# TK90X.net
KiCad netlist of a schematic drawn in EAGLE
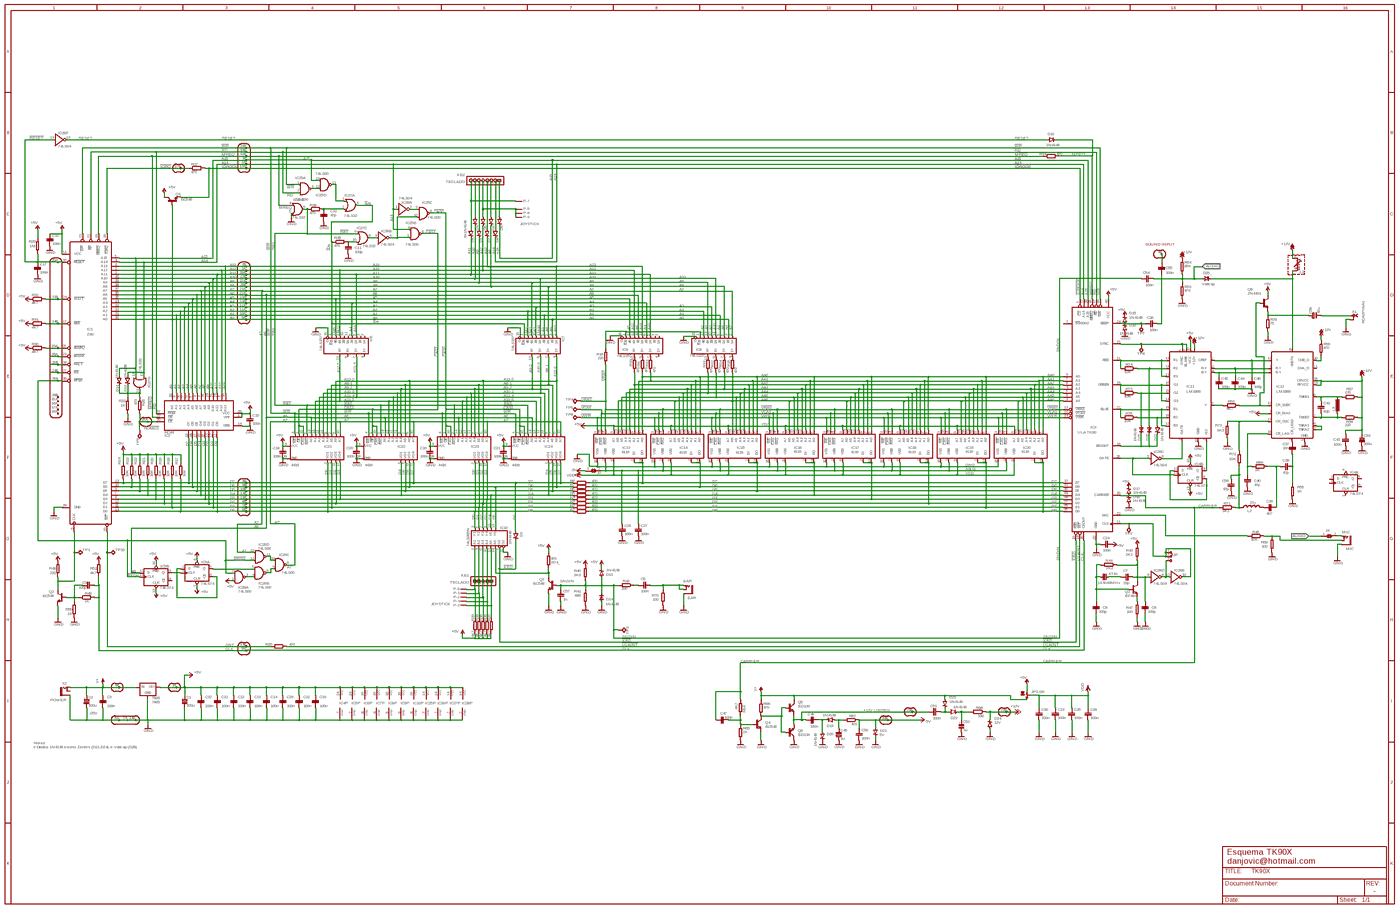
[diagram p0: schematic, sheet 1, overview]
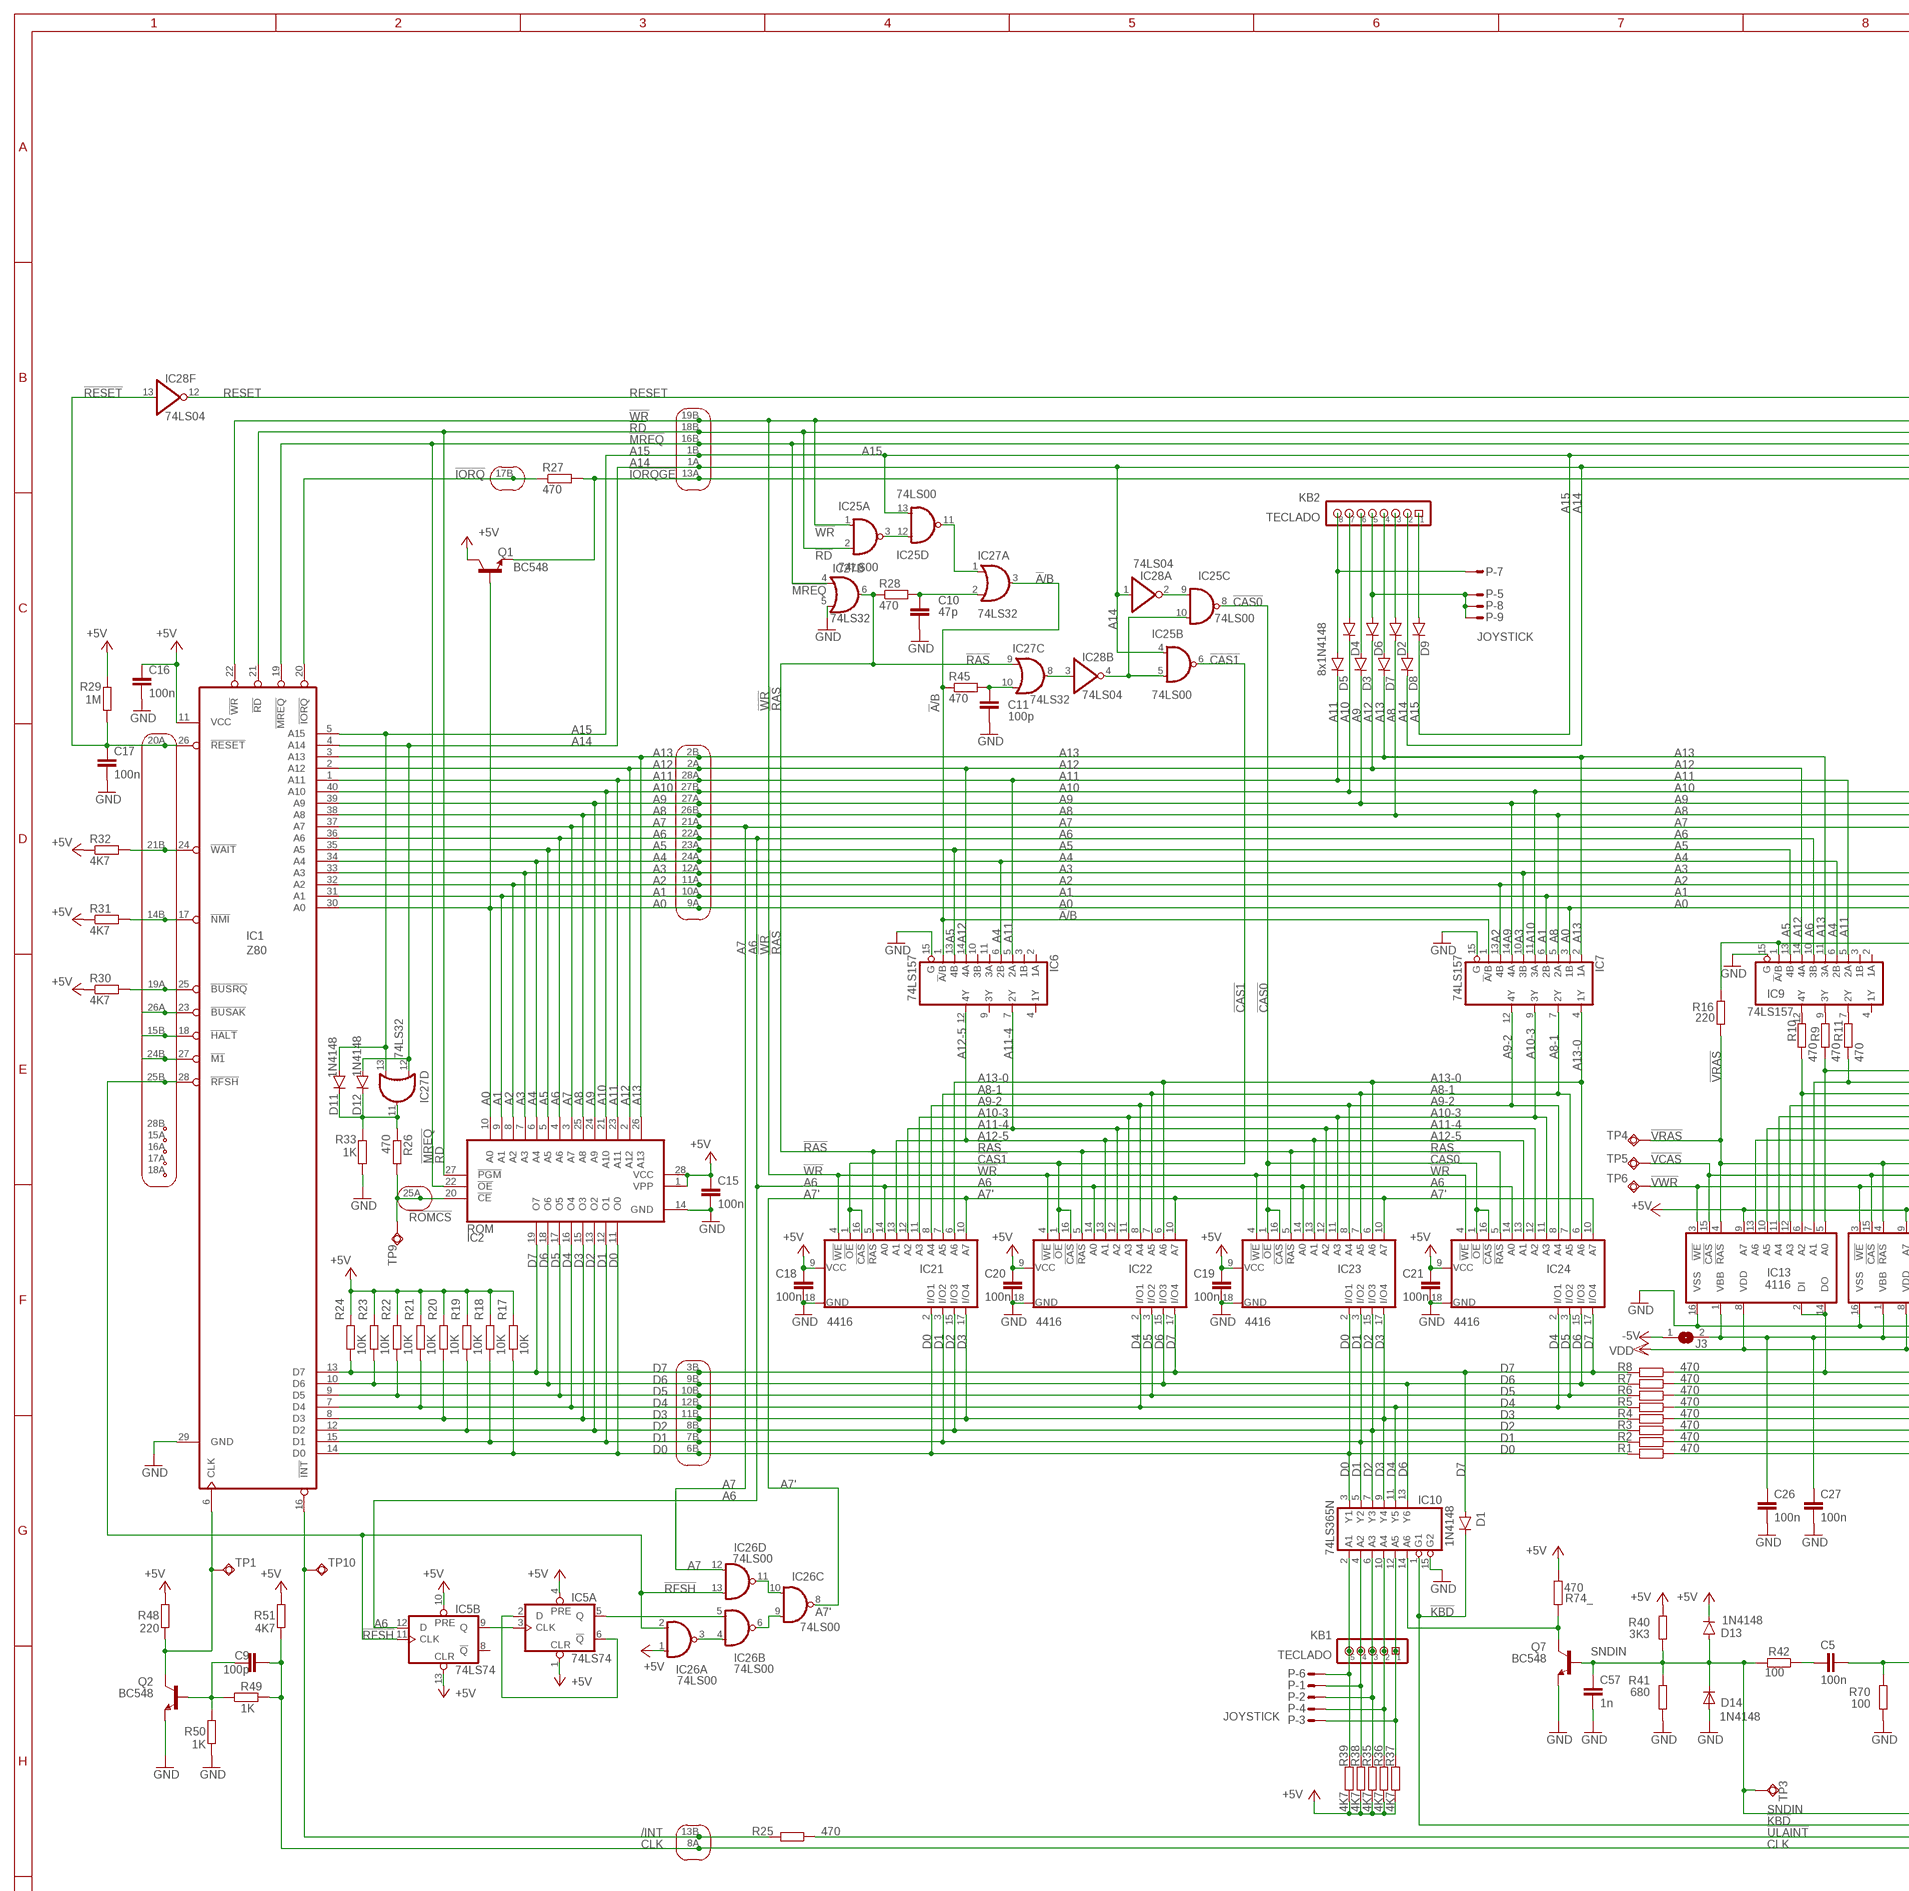
[diagram p1: schematic, sheet 1, part 1 of 4]
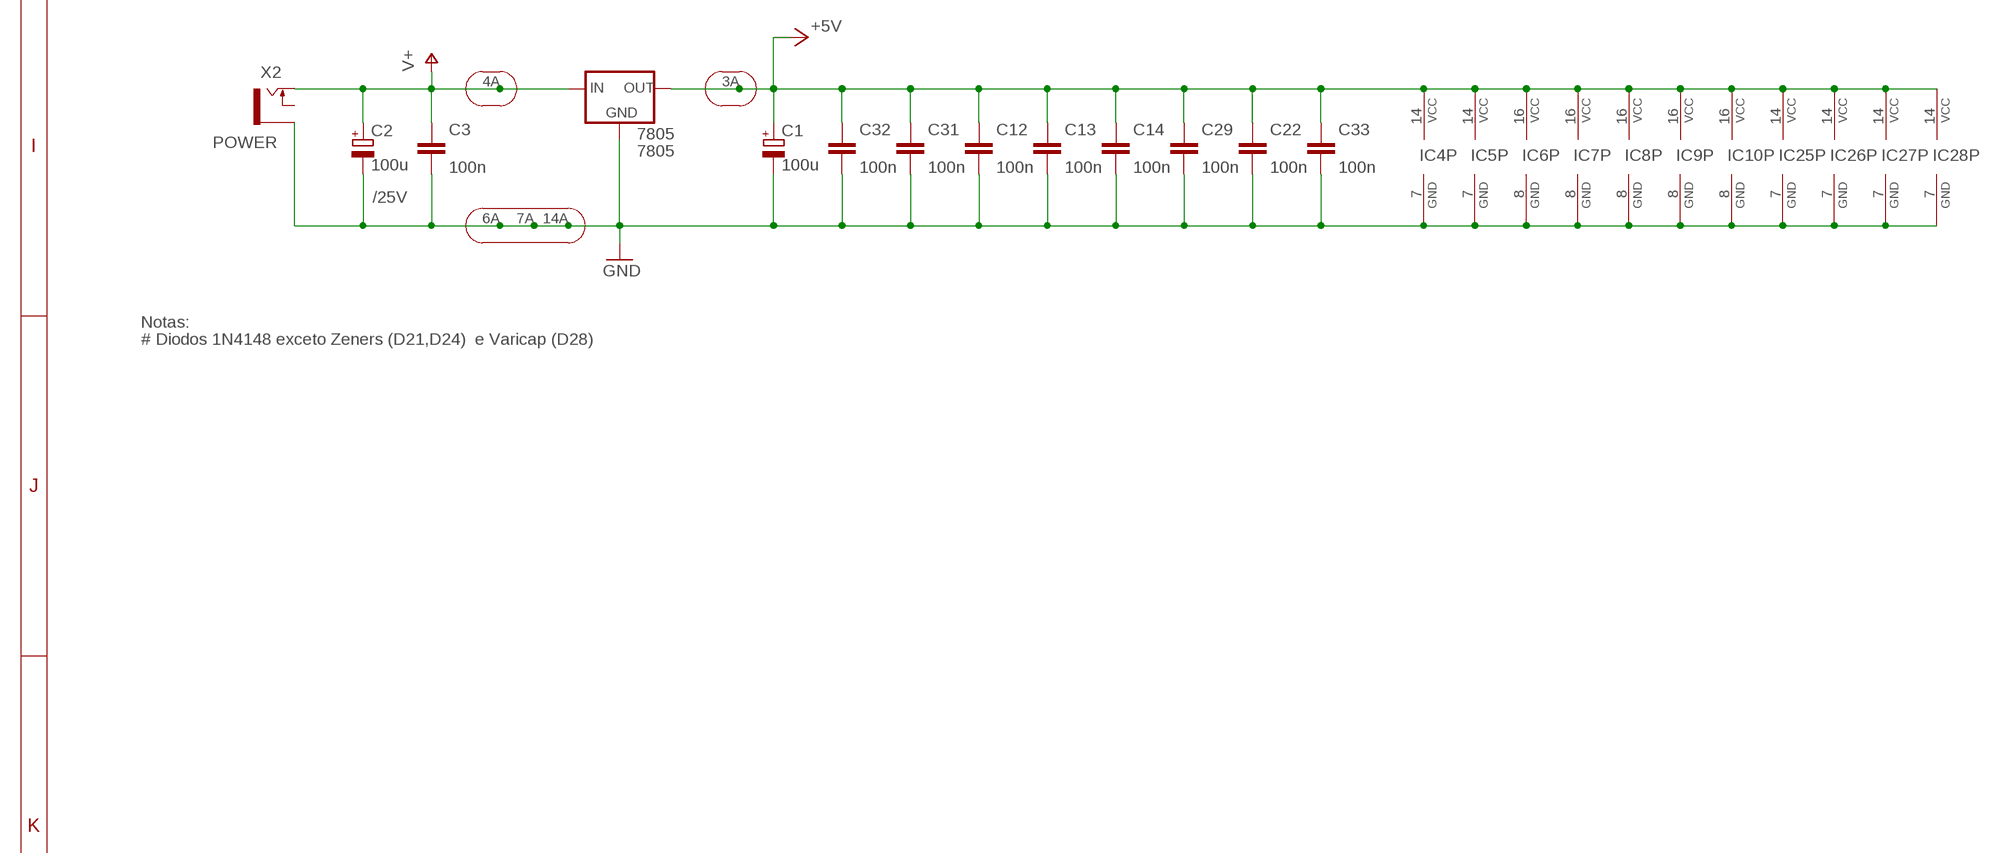
[diagram p2: schematic, sheet 1, part 2 of 4]
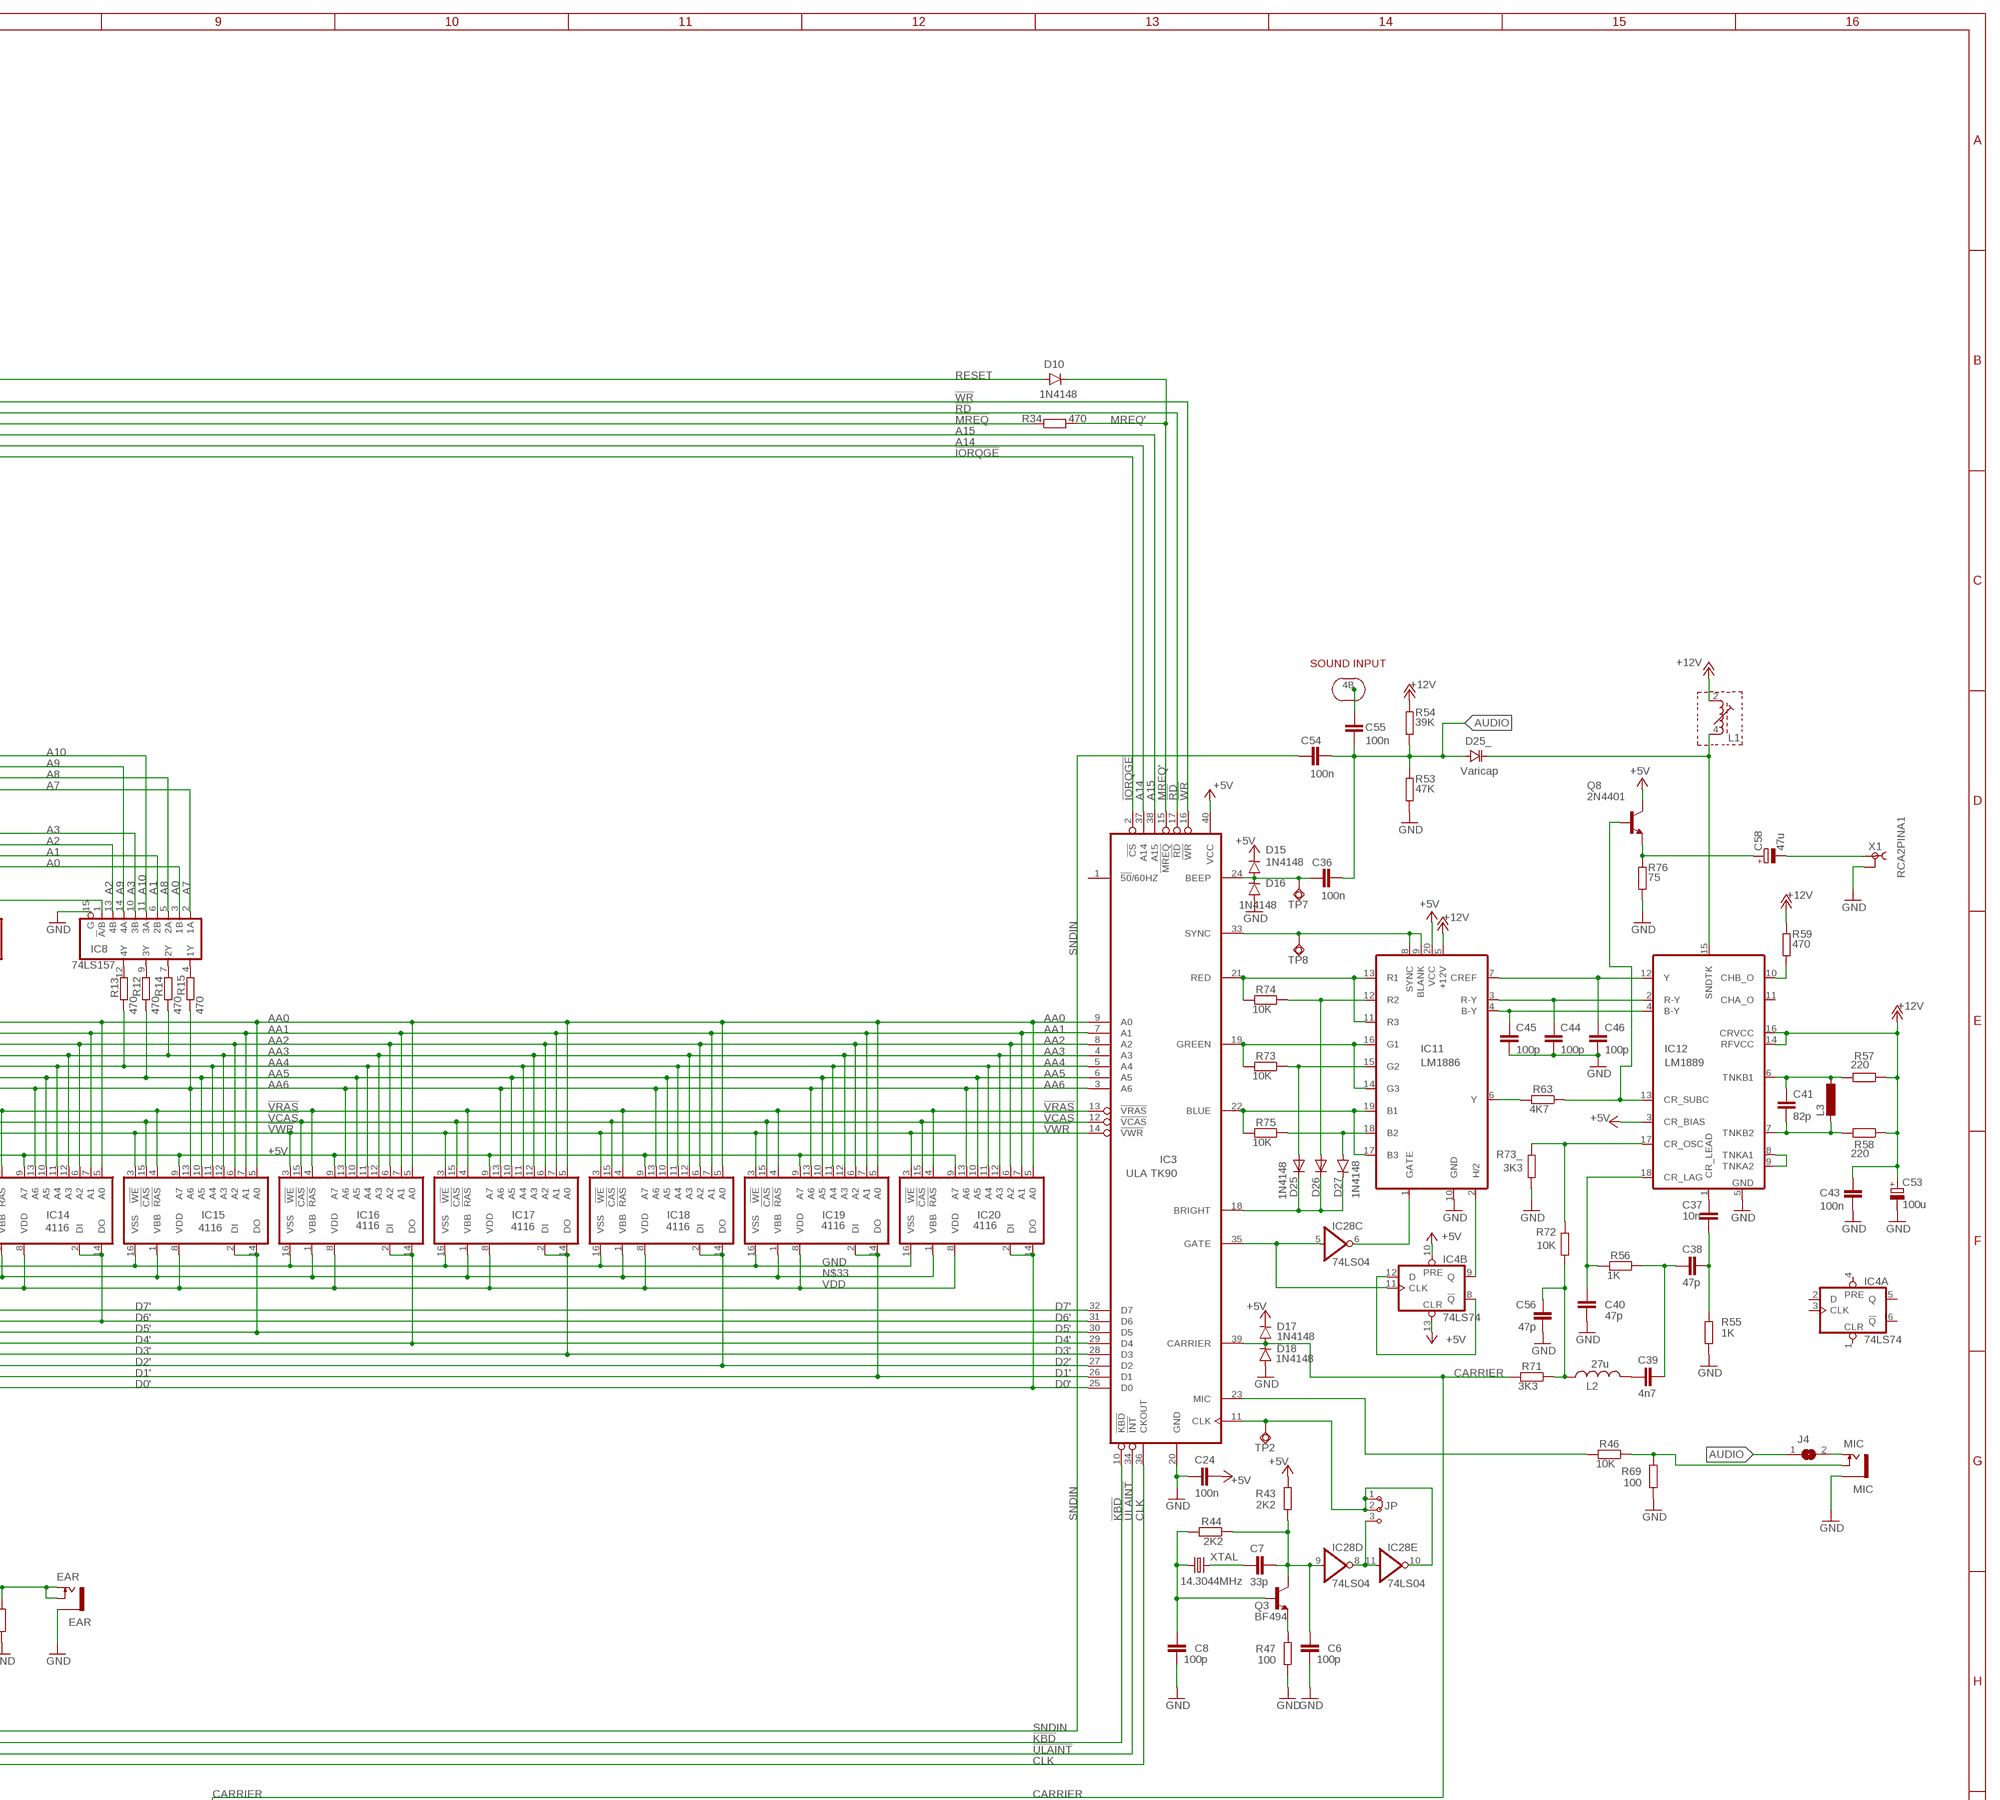
[diagram p3: schematic, sheet 1, part 3 of 4]
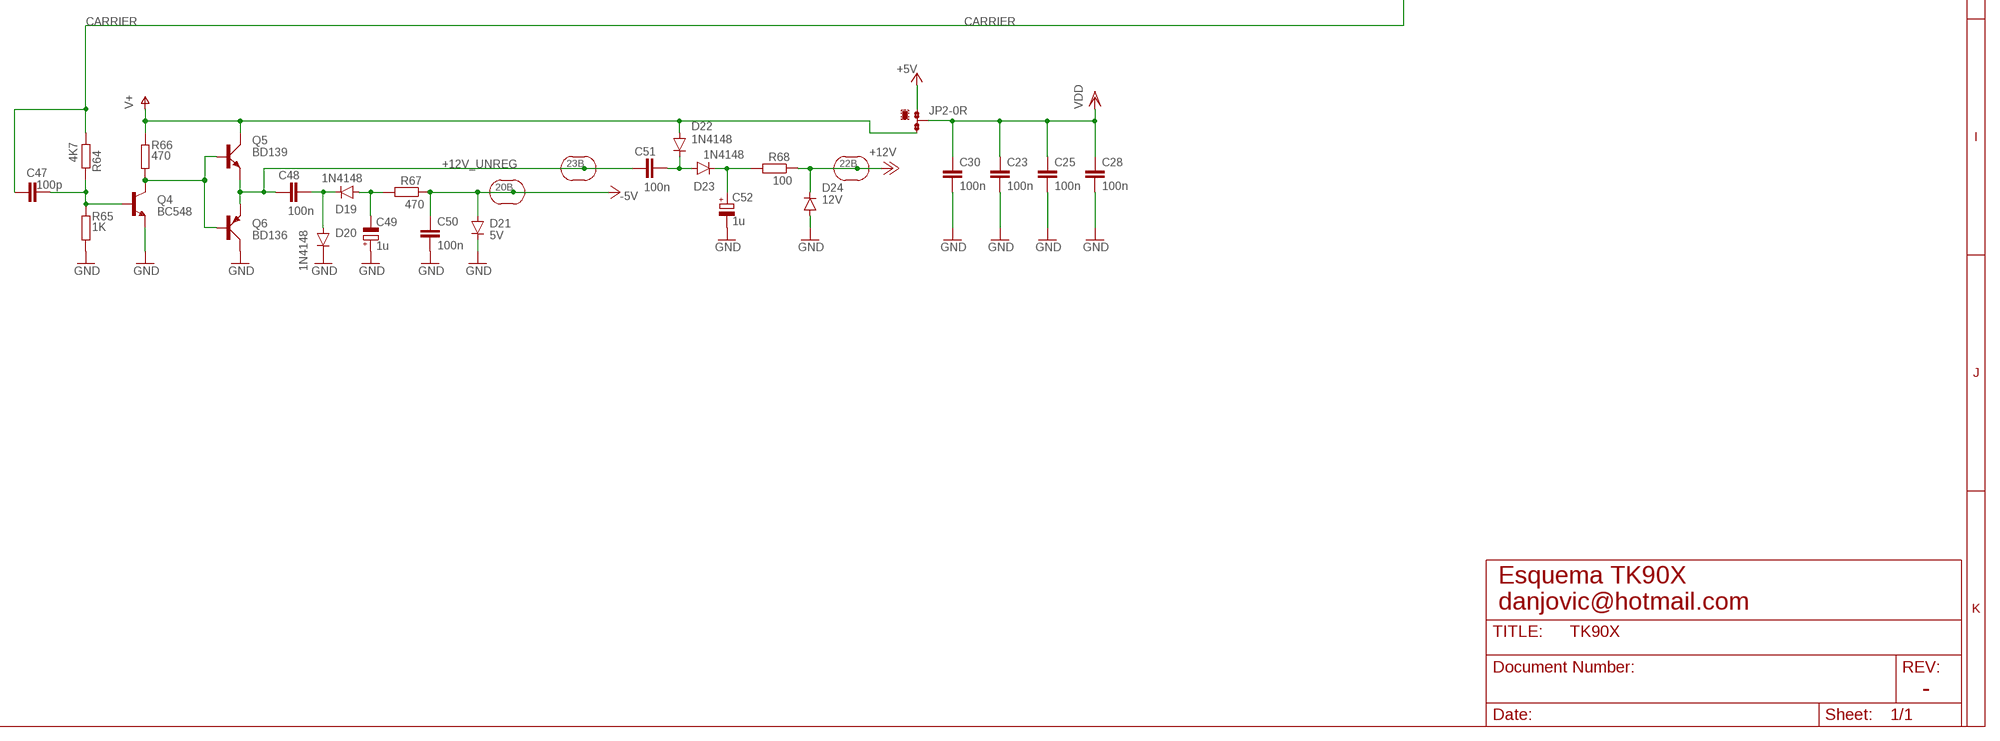
[diagram p4: schematic, sheet 1, part 4 of 4]

(export (version "E")
  (design (tool "Eeschema 10.0.6"))
  (components
    (comp (ref "7805")
      (value "7805")
      (footprint "eagle-import:78XXL")
      (libsource (lib "eagle-import") (part "78XXL"))
    )
    (comp (ref "C1")
      (value "100u")
      (footprint "eagle-import:E5-8,5")
      (libsource (lib "eagle-import") (part "CPOL-EUE5-8.5"))
    )
    (comp (ref "C2")
      (value "100u")
      (footprint "eagle-import:E5-8,5")
      (libsource (lib "eagle-import") (part "CPOL-EUE5-8.5"))
    )
    (comp (ref "C3")
      (value "100n")
      (footprint "eagle-import:C050-024X044")
      (libsource (lib "eagle-import") (part "C-EU050-024X044"))
    )
    (comp (ref "C5")
      (value "100n")
      (footprint "eagle-import:C050-024X044")
      (libsource (lib "eagle-import") (part "C-EU050-024X044"))
    )
    (comp (ref "C6")
      (value "100p")
      (footprint "eagle-import:C050-024X044")
      (libsource (lib "eagle-import") (part "C-EU050-024X044"))
    )
    (comp (ref "C7")
      (value "33p")
      (footprint "eagle-import:C050-024X044")
      (libsource (lib "eagle-import") (part "C-EU050-024X044"))
    )
    (comp (ref "C8")
      (value "100p")
      (footprint "eagle-import:C050-024X044")
      (libsource (lib "eagle-import") (part "C-EU050-024X044"))
    )
    (comp (ref "C9")
      (value "100p")
      (footprint "eagle-import:C050-024X044")
      (libsource (lib "eagle-import") (part "C-EU050-024X044"))
    )
    (comp (ref "C10")
      (value "47p")
      (footprint "eagle-import:C050-024X044")
      (libsource (lib "eagle-import") (part "C-EU050-024X044"))
    )
    (comp (ref "C11")
      (value "100p")
      (footprint "eagle-import:C050-024X044")
      (libsource (lib "eagle-import") (part "C-EU050-024X044"))
    )
    (comp (ref "C12")
      (value "100n")
      (footprint "eagle-import:C050-024X044")
      (libsource (lib "eagle-import") (part "C-EU050-024X044"))
    )
    (comp (ref "C13")
      (value "100n")
      (footprint "eagle-import:C050-024X044")
      (libsource (lib "eagle-import") (part "C-EU050-024X044"))
    )
    (comp (ref "C14")
      (value "100n")
      (footprint "eagle-import:C050-024X044")
      (libsource (lib "eagle-import") (part "C-EU050-024X044"))
    )
    (comp (ref "C15")
      (value "100n")
      (footprint "eagle-import:C050-024X044")
      (libsource (lib "eagle-import") (part "C-EU050-024X044"))
    )
    (comp (ref "C16")
      (value "100n")
      (footprint "eagle-import:C050-024X044")
      (libsource (lib "eagle-import") (part "C-EU050-024X044"))
    )
    (comp (ref "C17")
      (value "100n")
      (footprint "eagle-import:C050-024X044")
      (libsource (lib "eagle-import") (part "C-EU050-024X044"))
    )
    (comp (ref "C18")
      (value "100n")
      (footprint "eagle-import:C050-024X044")
      (libsource (lib "eagle-import") (part "C-EU050-024X044"))
    )
    (comp (ref "C19")
      (value "100n")
      (footprint "eagle-import:C050-024X044")
      (libsource (lib "eagle-import") (part "C-EU050-024X044"))
    )
    (comp (ref "C20")
      (value "100n")
      (footprint "eagle-import:C050-024X044")
      (libsource (lib "eagle-import") (part "C-EU050-024X044"))
    )
    (comp (ref "C21")
      (value "100n")
      (footprint "eagle-import:C050-024X044")
      (libsource (lib "eagle-import") (part "C-EU050-024X044"))
    )
    (comp (ref "C22")
      (value "100n")
      (footprint "eagle-import:C050-024X044")
      (libsource (lib "eagle-import") (part "C-EU050-024X044"))
    )
    (comp (ref "C23")
      (value "100n")
      (footprint "eagle-import:C050-024X044")
      (libsource (lib "eagle-import") (part "C-EU050-024X044"))
    )
    (comp (ref "C24")
      (value "100n")
      (footprint "eagle-import:C050-024X044")
      (libsource (lib "eagle-import") (part "C-EU050-024X044"))
    )
    (comp (ref "C25")
      (value "100n")
      (footprint "eagle-import:C050-024X044")
      (libsource (lib "eagle-import") (part "C-EU050-024X044"))
    )
    (comp (ref "C26")
      (value "100n")
      (footprint "eagle-import:C050-024X044")
      (libsource (lib "eagle-import") (part "C-EU050-024X044"))
    )
    (comp (ref "C27")
      (value "100n")
      (footprint "eagle-import:C050-024X044")
      (libsource (lib "eagle-import") (part "C-EU050-024X044"))
    )
    (comp (ref "C28")
      (value "100n")
      (footprint "eagle-import:C050-024X044")
      (libsource (lib "eagle-import") (part "C-EU050-024X044"))
    )
    (comp (ref "C29")
      (value "100n")
      (footprint "eagle-import:C050-024X044")
      (libsource (lib "eagle-import") (part "C-EU050-024X044"))
    )
    (comp (ref "C30")
      (value "100n")
      (footprint "eagle-import:C050-024X044")
      (libsource (lib "eagle-import") (part "C-EU050-024X044"))
    )
    (comp (ref "C31")
      (value "100n")
      (footprint "eagle-import:C050-024X044")
      (libsource (lib "eagle-import") (part "C-EU050-024X044"))
    )
    (comp (ref "C32")
      (value "100n")
      (footprint "eagle-import:C050-024X044")
      (libsource (lib "eagle-import") (part "C-EU050-024X044"))
    )
    (comp (ref "C33")
      (value "100n")
      (footprint "eagle-import:C050-024X044")
      (libsource (lib "eagle-import") (part "C-EU050-024X044"))
    )
    (comp (ref "C36")
      (value "100n")
      (footprint "eagle-import:C050-024X044")
      (libsource (lib "eagle-import") (part "C-EU050-024X044"))
    )
    (comp (ref "C37")
      (value "10n")
      (footprint "eagle-import:C050-024X044")
      (libsource (lib "eagle-import") (part "C-EU050-024X044"))
    )
    (comp (ref "C38")
      (value "47p")
      (footprint "eagle-import:C050-024X044")
      (libsource (lib "eagle-import") (part "C-EU050-024X044"))
    )
    (comp (ref "C39")
      (value "4n7")
      (footprint "eagle-import:C050-024X044")
      (libsource (lib "eagle-import") (part "C-EU050-024X044"))
    )
    (comp (ref "C40")
      (value "47p")
      (footprint "eagle-import:C050-024X044")
      (libsource (lib "eagle-import") (part "C-EU050-024X044"))
    )
    (comp (ref "C41")
      (value "82p")
      (footprint "eagle-import:C050-024X044")
      (libsource (lib "eagle-import") (part "C-EU050-024X044"))
    )
    (comp (ref "C43")
      (value "100n")
      (footprint "eagle-import:C050-024X044")
      (libsource (lib "eagle-import") (part "C-EU050-024X044"))
    )
    (comp (ref "C44")
      (value "100p")
      (footprint "eagle-import:C050-024X044")
      (libsource (lib "eagle-import") (part "C-EU050-024X044"))
    )
    (comp (ref "C45")
      (value "100p")
      (footprint "eagle-import:C050-024X044")
      (libsource (lib "eagle-import") (part "C-EU050-024X044"))
    )
    (comp (ref "C46")
      (value "100p")
      (footprint "eagle-import:C050-024X044")
      (libsource (lib "eagle-import") (part "C-EU050-024X044"))
    )
    (comp (ref "C47")
      (value "100p")
      (footprint "eagle-import:C050-024X044")
      (libsource (lib "eagle-import") (part "C-EU050-024X044"))
    )
    (comp (ref "C48")
      (value "100n")
      (footprint "eagle-import:C050-024X044")
      (libsource (lib "eagle-import") (part "C-EU050-024X044"))
    )
    (comp (ref "C49")
      (value "1u")
      (footprint "eagle-import:E2-4")
      (libsource (lib "eagle-import") (part "CPOL-EUE2-4"))
    )
    (comp (ref "C50")
      (value "100n")
      (footprint "eagle-import:C050-024X044")
      (libsource (lib "eagle-import") (part "C-EU050-024X044"))
    )
    (comp (ref "C51")
      (value "100n")
      (footprint "eagle-import:C050-024X044")
      (libsource (lib "eagle-import") (part "C-EU050-024X044"))
    )
    (comp (ref "C52")
      (value "1u")
      (footprint "eagle-import:E2-5")
      (libsource (lib "eagle-import") (part "CPOL-EUE2-5"))
    )
    (comp (ref "C53")
      (value "100u")
      (footprint "eagle-import:E5-4")
      (libsource (lib "eagle-import") (part "CPOL-EUE5-4"))
    )
    (comp (ref "C54")
      (value "100n")
      (footprint "eagle-import:C050-024X044")
      (libsource (lib "eagle-import") (part "C-EU050-024X044"))
    )
    (comp (ref "C55")
      (value "100n")
      (footprint "eagle-import:C050-024X044")
      (libsource (lib "eagle-import") (part "C-EU050-024X044"))
    )
    (comp (ref "C56")
      (value "47p")
      (footprint "eagle-import:C050-024X044")
      (libsource (lib "eagle-import") (part "C-EU050-024X044"))
    )
    (comp (ref "C57")
      (value "1n")
      (footprint "eagle-import:C050-024X044")
      (libsource (lib "eagle-import") (part "C-EU050-024X044"))
    )
    (comp (ref "C58")
      (value "47u")
      (footprint "eagle-import:E5-4")
      (libsource (lib "eagle-import") (part "CPOL-EUE5-4"))
    )
    (comp (ref "D1")
      (value "1N4148")
      (footprint "eagle-import:DO35-12")
      (libsource (lib "eagle-import") (part "DDO35-12"))
    )
    (comp (ref "D2")
      (value "1N4148")
      (footprint "eagle-import:DO35-12")
      (libsource (lib "eagle-import") (part "DDO35-12"))
    )
    (comp (ref "D3")
      (value "1N4148")
      (footprint "eagle-import:DO35-12")
      (libsource (lib "eagle-import") (part "DDO35-12"))
    )
    (comp (ref "D4")
      (value "1N4148")
      (footprint "eagle-import:DO35-12")
      (libsource (lib "eagle-import") (part "DDO35-12"))
    )
    (comp (ref "D5")
      (value "1N4148")
      (footprint "eagle-import:DO35-12")
      (libsource (lib "eagle-import") (part "DDO35-12"))
    )
    (comp (ref "D6")
      (value "1N4148")
      (footprint "eagle-import:DO35-12")
      (libsource (lib "eagle-import") (part "DDO35-12"))
    )
    (comp (ref "D7")
      (value "1N4148")
      (footprint "eagle-import:DO35-12")
      (libsource (lib "eagle-import") (part "DDO35-12"))
    )
    (comp (ref "D8")
      (value "1N4148")
      (footprint "eagle-import:DO35-12")
      (libsource (lib "eagle-import") (part "DDO35-12"))
    )
    (comp (ref "D9")
      (value "1N4148")
      (footprint "eagle-import:DO35-12")
      (libsource (lib "eagle-import") (part "DDO35-12"))
    )
    (comp (ref "D10")
      (value "1N4148")
      (footprint "eagle-import:DO35-12")
      (libsource (lib "eagle-import") (part "DDO35-12"))
    )
    (comp (ref "D11")
      (value "1N4148")
      (footprint "eagle-import:DO35-12")
      (libsource (lib "eagle-import") (part "DDO35-12"))
    )
    (comp (ref "D12")
      (value "1N4148")
      (footprint "eagle-import:DO35-12")
      (libsource (lib "eagle-import") (part "DDO35-12"))
    )
    (comp (ref "D13")
      (value "1N4148")
      (footprint "eagle-import:DO35-12")
      (libsource (lib "eagle-import") (part "DDO35-12"))
    )
    (comp (ref "D14")
      (value "1N4148")
      (footprint "eagle-import:D-5")
      (libsource (lib "eagle-import") (part "DIODE-D-5"))
    )
    (comp (ref "D15")
      (value "1N4148")
      (footprint "eagle-import:DO35-12")
      (libsource (lib "eagle-import") (part "DDO35-12"))
    )
    (comp (ref "D16")
      (value "1N4148")
      (footprint "eagle-import:DO35-12")
      (libsource (lib "eagle-import") (part "DDO35-12"))
    )
    (comp (ref "D17")
      (value "1N4148")
      (footprint "eagle-import:DO35-12")
      (libsource (lib "eagle-import") (part "DDO35-12"))
    )
    (comp (ref "D18")
      (value "1N4148")
      (footprint "eagle-import:DO35-12")
      (libsource (lib "eagle-import") (part "DDO35-12"))
    )
    (comp (ref "D19")
      (value "1N4148")
      (footprint "eagle-import:DO35-12")
      (libsource (lib "eagle-import") (part "DDO35-12"))
    )
    (comp (ref "D20")
      (value "1N4148")
      (footprint "eagle-import:DO35-12")
      (libsource (lib "eagle-import") (part "DDO35-12"))
    )
    (comp (ref "D21")
      (value "5V")
      (footprint "eagle-import:DO35-12")
      (libsource (lib "eagle-import") (part "DDO35-12"))
    )
    (comp (ref "D22")
      (value "1N4148")
      (footprint "eagle-import:DO35-12")
      (libsource (lib "eagle-import") (part "DDO35-12"))
    )
    (comp (ref "D23")
      (value "1N4148")
      (footprint "eagle-import:DO35-12")
      (libsource (lib "eagle-import") (part "DDO35-12"))
    )
    (comp (ref "D24")
      (value "12V")
      (footprint "eagle-import:DO35-12")
      (libsource (lib "eagle-import") (part "DDO35-12"))
    )
    (comp (ref "D25")
      (value "1N4148")
      (footprint "eagle-import:D-5")
      (libsource (lib "eagle-import") (part "DIODE-D-5"))
    )
    (comp (ref "D25_")
      (value "Varicap")
      (footprint "eagle-import:D200")
      (libsource (lib "eagle-import") (part "VARICAP-200"))
    )
    (comp (ref "D26")
      (value "1N4148")
      (footprint "eagle-import:D-5")
      (libsource (lib "eagle-import") (part "DIODE-D-5"))
    )
    (comp (ref "D27")
      (value "1N4148")
      (footprint "eagle-import:DO35-12")
      (libsource (lib "eagle-import") (part "DDO35-12"))
    )
    (comp (ref "EAR")
      (value "EAR")
      (footprint "eagle-import:MONO")
      (libsource (lib "eagle-import") (part "JACK?-MONO"))
    )
    (comp (ref "IC1")
      (value "Z80")
      (footprint "eagle-import:DIL40")
      (libsource (lib "eagle-import") (part "Z80CPU"))
    )
    (comp (ref "IC2")
      (value "ROM")
      (footprint "eagle-import:DIL28")
      (libsource (lib "eagle-import") (part "25128"))
    )
    (comp (ref "IC3")
      (value "ULA TK90")
      (footprint "eagle-import:DIL40")
      (libsource (lib "eagle-import") (part "ULA-TK90"))
    )
    (comp (ref "IC4")
      (value "74LS74")
      (footprint "eagle-import:DIL14")
      (libsource (lib "eagle-import") (part "7474NLS"))
    )
    (comp (ref "IC5")
      (value "74LS74")
      (footprint "eagle-import:DIL14")
      (libsource (lib "eagle-import") (part "7474NLS"))
    )
    (comp (ref "IC6")
      (value "74LS157")
      (footprint "eagle-import:DIL16")
      (libsource (lib "eagle-import") (part "74157NS"))
    )
    (comp (ref "IC7")
      (value "74LS157")
      (footprint "eagle-import:DIL16")
      (libsource (lib "eagle-import") (part "74157NS"))
    )
    (comp (ref "IC8")
      (value "74LS157")
      (footprint "eagle-import:DIL16")
      (libsource (lib "eagle-import") (part "74157NS"))
    )
    (comp (ref "IC9")
      (value "74LS157")
      (footprint "eagle-import:DIL16")
      (libsource (lib "eagle-import") (part "74157NS"))
    )
    (comp (ref "IC10")
      (value "74LS365N")
      (footprint "eagle-import:DIL16")
      (libsource (lib "eagle-import") (part "74365NLS"))
    )
    (comp (ref "IC11")
      (value "LM1886")
      (footprint "eagle-import:DIL20")
      (libsource (lib "eagle-import") (part "LM1886N"))
    )
    (comp (ref "IC12")
      (value "LM1889")
      (footprint "eagle-import:DIL18")
      (libsource (lib "eagle-import") (part "LM1889"))
    )
    (comp (ref "IC13")
      (value "4116")
      (footprint "eagle-import:DIL16")
      (libsource (lib "eagle-import") (part "MK4516"))
    )
    (comp (ref "IC14")
      (value "4116")
      (footprint "eagle-import:DIL16")
      (libsource (lib "eagle-import") (part "MK4516"))
    )
    (comp (ref "IC15")
      (value "4116")
      (footprint "eagle-import:DIL16")
      (libsource (lib "eagle-import") (part "MK4516"))
    )
    (comp (ref "IC16")
      (value "4116")
      (footprint "eagle-import:DIL16")
      (libsource (lib "eagle-import") (part "MK4516"))
    )
    (comp (ref "IC17")
      (value "4116")
      (footprint "eagle-import:DIL16")
      (libsource (lib "eagle-import") (part "MK4516"))
    )
    (comp (ref "IC18")
      (value "4116")
      (footprint "eagle-import:DIL16")
      (libsource (lib "eagle-import") (part "MK4516"))
    )
    (comp (ref "IC19")
      (value "4116")
      (footprint "eagle-import:DIL16")
      (libsource (lib "eagle-import") (part "MK4516"))
    )
    (comp (ref "IC20")
      (value "4116")
      (footprint "eagle-import:DIL16")
      (libsource (lib "eagle-import") (part "MK4516"))
    )
    (comp (ref "IC21")
      (value "4416")
      (footprint "eagle-import:DIL18")
      (libsource (lib "eagle-import") (part "4416"))
    )
    (comp (ref "IC22")
      (value "4416")
      (footprint "eagle-import:DIL18")
      (libsource (lib "eagle-import") (part "4416"))
    )
    (comp (ref "IC23")
      (value "4416")
      (footprint "eagle-import:DIL18")
      (libsource (lib "eagle-import") (part "4416"))
    )
    (comp (ref "IC24")
      (value "4416")
      (footprint "eagle-import:DIL18")
      (libsource (lib "eagle-import") (part "4416"))
    )
    (comp (ref "IC25")
      (value "74LS00")
      (footprint "eagle-import:DIL14")
      (libsource (lib "eagle-import") (part "7400NLS"))
    )
    (comp (ref "IC26")
      (value "74LS00")
      (footprint "eagle-import:DIL14")
      (libsource (lib "eagle-import") (part "7400NLS"))
    )
    (comp (ref "IC27")
      (value "74LS32")
      (footprint "eagle-import:DIL14")
      (libsource (lib "eagle-import") (part "7432NLS"))
    )
    (comp (ref "IC28")
      (value "74LS04")
      (footprint "eagle-import:DIL14")
      (libsource (lib "eagle-import") (part "7404NLS"))
    )
    (comp (ref "J3") (value "SJ") (footprint "eagle-import:SJ") (libsource (lib "eagle-import") (part "SJ")))
    (comp (ref "J4") (value "SJ") (footprint "eagle-import:SJ") (libsource (lib "eagle-import") (part "SJ")))
    (comp (ref "JP")
      (value "J2X1MM")
      (footprint "eagle-import:03C")
      (libsource (lib "eagle-import") (part "J2X1MM"))
    )
    (comp (ref "JP2")
      (value "0R-JUMPB")
      (footprint "eagle-import:B0R-JMP")
      (libsource (lib "eagle-import") (part "0R-JUMPB"))
    )
    (comp (ref "KB1")
      (value "TECLADO")
      (footprint "eagle-import:FE05-1")
      (libsource (lib "eagle-import") (part "CON-TECL-5"))
    )
    (comp (ref "KB2")
      (value "TECLADO")
      (footprint "eagle-import:FE08")
      (libsource (lib "eagle-import") (part "CON-TECL-8"))
    )
    (comp (ref "L1")
      (value "COIL")
      (footprint "eagle-import:COIL")
      (libsource (lib "eagle-import") (part "COIL"))
    )
    (comp (ref "L2")
      (value "27u")
      (footprint "eagle-import:0207_7")
      (libsource (lib "eagle-import") (part "L-US0207/7"))
    )
    (comp (ref "L3")
      (value "L-EU0204/5")
      (footprint "eagle-import:0204_5")
      (libsource (lib "eagle-import") (part "L-EU0204/5"))
    )
    (comp (ref "MIC")
      (value "MIC")
      (footprint "eagle-import:MONO")
      (libsource (lib "eagle-import") (part "JACK?-MONO"))
    )
    (comp (ref "P")
      (value "JOYSTICK")
      (footprint "eagle-import:177-009-MALE")
      (libsource (lib "eagle-import") (part "M09?S.590"))
    )
    (comp (ref "Q1")
      (value "BC548")
      (footprint "eagle-import:TO92L")
      (libsource (lib "eagle-import") (part "-NPN-TO92L"))
    )
    (comp (ref "Q2")
      (value "BC548")
      (footprint "eagle-import:TO92L")
      (libsource (lib "eagle-import") (part "-NPN-TO92L"))
    )
    (comp (ref "Q3")
      (value "BF494")
      (footprint "eagle-import:TO92-CEB")
      (libsource (lib "eagle-import") (part "BF494"))
    )
    (comp (ref "Q4")
      (value "BC548")
      (footprint "eagle-import:TO92L")
      (libsource (lib "eagle-import") (part "-NPN-TO92L"))
    )
    (comp (ref "Q5")
      (value "BD139")
      (footprint "eagle-import:TO126AV")
      (libsource (lib "eagle-import") (part "BD139"))
    )
    (comp (ref "Q6")
      (value "BD136")
      (footprint "eagle-import:TO126AV")
      (libsource (lib "eagle-import") (part "BD140"))
    )
    (comp (ref "Q7")
      (value "BC548")
      (footprint "eagle-import:TO92L")
      (libsource (lib "eagle-import") (part "-NPN-TO92L"))
    )
    (comp (ref "Q8")
      (value "2N4401")
      (footprint "eagle-import:TO92-EBC")
      (libsource (lib "eagle-import") (part "2N4401"))
    )
    (comp (ref "R1")
      (value "470")
      (footprint "eagle-import:0207_12")
      (libsource (lib "eagle-import") (part "R-EU_0207/12"))
    )
    (comp (ref "R2")
      (value "470")
      (footprint "eagle-import:0207_12")
      (libsource (lib "eagle-import") (part "R-EU_0207/12"))
    )
    (comp (ref "R3")
      (value "470")
      (footprint "eagle-import:0207_12")
      (libsource (lib "eagle-import") (part "R-EU_0207/12"))
    )
    (comp (ref "R4")
      (value "470")
      (footprint "eagle-import:0207_12")
      (libsource (lib "eagle-import") (part "R-EU_0207/12"))
    )
    (comp (ref "R5")
      (value "470")
      (footprint "eagle-import:0207_12")
      (libsource (lib "eagle-import") (part "R-EU_0207/12"))
    )
    (comp (ref "R6")
      (value "470")
      (footprint "eagle-import:0207_12")
      (libsource (lib "eagle-import") (part "R-EU_0207/12"))
    )
    (comp (ref "R7")
      (value "470")
      (footprint "eagle-import:0207_12")
      (libsource (lib "eagle-import") (part "R-EU_0207/12"))
    )
    (comp (ref "R8")
      (value "470")
      (footprint "eagle-import:0207_12")
      (libsource (lib "eagle-import") (part "R-EU_0207/12"))
    )
    (comp (ref "R9")
      (value "470")
      (footprint "eagle-import:0207_12")
      (libsource (lib "eagle-import") (part "R-EU_0207/12"))
    )
    (comp (ref "R10")
      (value "470")
      (footprint "eagle-import:0207_12")
      (libsource (lib "eagle-import") (part "R-EU_0207/12"))
    )
    (comp (ref "R11")
      (value "470")
      (footprint "eagle-import:0207_12")
      (libsource (lib "eagle-import") (part "R-EU_0207/12"))
    )
    (comp (ref "R12")
      (value "470")
      (footprint "eagle-import:0207_12")
      (libsource (lib "eagle-import") (part "R-EU_0207/12"))
    )
    (comp (ref "R13")
      (value "470")
      (footprint "eagle-import:0207_12")
      (libsource (lib "eagle-import") (part "R-EU_0207/12"))
    )
    (comp (ref "R14")
      (value "470")
      (footprint "eagle-import:0207_12")
      (libsource (lib "eagle-import") (part "R-EU_0207/12"))
    )
    (comp (ref "R15")
      (value "470")
      (footprint "eagle-import:0207_12")
      (libsource (lib "eagle-import") (part "R-EU_0207/12"))
    )
    (comp (ref "R16")
      (value "220")
      (footprint "eagle-import:0207_12")
      (libsource (lib "eagle-import") (part "R-EU_0207/12"))
    )
    (comp (ref "R17")
      (value "10K")
      (footprint "eagle-import:0207_12")
      (libsource (lib "eagle-import") (part "R-EU_0207/12"))
    )
    (comp (ref "R18")
      (value "10K")
      (footprint "eagle-import:0207_12")
      (libsource (lib "eagle-import") (part "R-EU_0207/12"))
    )
    (comp (ref "R19")
      (value "10K")
      (footprint "eagle-import:0207_12")
      (libsource (lib "eagle-import") (part "R-EU_0207/12"))
    )
    (comp (ref "R20")
      (value "10K")
      (footprint "eagle-import:0207_12")
      (libsource (lib "eagle-import") (part "R-EU_0207/12"))
    )
    (comp (ref "R21")
      (value "10K")
      (footprint "eagle-import:0207_12")
      (libsource (lib "eagle-import") (part "R-EU_0207/12"))
    )
    (comp (ref "R22")
      (value "10K")
      (footprint "eagle-import:0207_12")
      (libsource (lib "eagle-import") (part "R-EU_0207/12"))
    )
    (comp (ref "R23")
      (value "10K")
      (footprint "eagle-import:0207_12")
      (libsource (lib "eagle-import") (part "R-EU_0207/12"))
    )
    (comp (ref "R24")
      (value "10K")
      (footprint "eagle-import:0207_12")
      (libsource (lib "eagle-import") (part "R-EU_0207/12"))
    )
    (comp (ref "R25")
      (value "470")
      (footprint "eagle-import:0207_12")
      (libsource (lib "eagle-import") (part "R-EU_0207/12"))
    )
    (comp (ref "R26")
      (value "470")
      (footprint "eagle-import:0207_12")
      (libsource (lib "eagle-import") (part "R-EU_0207/12"))
    )
    (comp (ref "R27")
      (value "470")
      (footprint "eagle-import:0207_12")
      (libsource (lib "eagle-import") (part "R-EU_0207/12"))
    )
    (comp (ref "R28")
      (value "470")
      (footprint "eagle-import:0207_12")
      (libsource (lib "eagle-import") (part "R-EU_0207/12"))
    )
    (comp (ref "R29")
      (value "1M")
      (footprint "eagle-import:0207_12")
      (libsource (lib "eagle-import") (part "R-EU_0207/12"))
    )
    (comp (ref "R30")
      (value "4K7")
      (footprint "eagle-import:0207_12")
      (libsource (lib "eagle-import") (part "R-EU_0207/12"))
    )
    (comp (ref "R31")
      (value "4K7")
      (footprint "eagle-import:0207_12")
      (libsource (lib "eagle-import") (part "R-EU_0207/12"))
    )
    (comp (ref "R32")
      (value "4K7")
      (footprint "eagle-import:0207_12")
      (libsource (lib "eagle-import") (part "R-EU_0207/12"))
    )
    (comp (ref "R33")
      (value "1K")
      (footprint "eagle-import:0207_12")
      (libsource (lib "eagle-import") (part "R-EU_0207/12"))
    )
    (comp (ref "R34")
      (value "470")
      (footprint "eagle-import:0207_12")
      (libsource (lib "eagle-import") (part "R-EU_0207/12"))
    )
    (comp (ref "R35")
      (value "4K7")
      (footprint "eagle-import:0207_12")
      (libsource (lib "eagle-import") (part "R-EU_0207/12"))
    )
    (comp (ref "R36")
      (value "4K7")
      (footprint "eagle-import:0207_12")
      (libsource (lib "eagle-import") (part "R-EU_0207/12"))
    )
    (comp (ref "R37")
      (value "4K7")
      (footprint "eagle-import:0207_12")
      (libsource (lib "eagle-import") (part "R-EU_0207/12"))
    )
    (comp (ref "R38")
      (value "4K7")
      (footprint "eagle-import:0207_12")
      (libsource (lib "eagle-import") (part "R-EU_0207/12"))
    )
    (comp (ref "R39")
      (value "4K7")
      (footprint "eagle-import:0207_12")
      (libsource (lib "eagle-import") (part "R-EU_0207/12"))
    )
    (comp (ref "R40")
      (value "3K3")
      (footprint "eagle-import:0207_12")
      (libsource (lib "eagle-import") (part "R-EU_0207/12"))
    )
    (comp (ref "R41")
      (value "680")
      (footprint "eagle-import:0207_5V")
      (libsource (lib "eagle-import") (part "R-EU_0207/5V"))
    )
    (comp (ref "R42")
      (value "100")
      (footprint "eagle-import:0207_5V")
      (libsource (lib "eagle-import") (part "R-EU_0207/5V"))
    )
    (comp (ref "R43")
      (value "2K2")
      (footprint "eagle-import:0207_12")
      (libsource (lib "eagle-import") (part "R-EU_0207/12"))
    )
    (comp (ref "R44")
      (value "2K2")
      (footprint "eagle-import:0207_12")
      (libsource (lib "eagle-import") (part "R-EU_0207/12"))
    )
    (comp (ref "R45")
      (value "470")
      (footprint "eagle-import:0207_12")
      (libsource (lib "eagle-import") (part "R-EU_0207/12"))
    )
    (comp (ref "R46")
      (value "10K")
      (footprint "eagle-import:0207_12")
      (libsource (lib "eagle-import") (part "R-EU_0207/12"))
    )
    (comp (ref "R47")
      (value "100")
      (footprint "eagle-import:0207_12")
      (libsource (lib "eagle-import") (part "R-EU_0207/12"))
    )
    (comp (ref "R48")
      (value "220")
      (footprint "eagle-import:0207_12")
      (libsource (lib "eagle-import") (part "R-EU_0207/12"))
    )
    (comp (ref "R49")
      (value "1K")
      (footprint "eagle-import:0207_12")
      (libsource (lib "eagle-import") (part "R-EU_0207/12"))
    )
    (comp (ref "R50")
      (value "1K")
      (footprint "eagle-import:0207_12")
      (libsource (lib "eagle-import") (part "R-EU_0207/12"))
    )
    (comp (ref "R51")
      (value "4K7")
      (footprint "eagle-import:0207_12")
      (libsource (lib "eagle-import") (part "R-EU_0207/12"))
    )
    (comp (ref "R53")
      (value "47K")
      (footprint "eagle-import:0207_12")
      (libsource (lib "eagle-import") (part "R-EU_0207/12"))
    )
    (comp (ref "R54")
      (value "39K")
      (footprint "eagle-import:0207_12")
      (libsource (lib "eagle-import") (part "R-EU_0207/12"))
    )
    (comp (ref "R55")
      (value "1K")
      (footprint "eagle-import:0207_5V")
      (libsource (lib "eagle-import") (part "R-EU_0207/5V"))
    )
    (comp (ref "R56")
      (value "1K")
      (footprint "eagle-import:0207_5V")
      (libsource (lib "eagle-import") (part "R-EU_0207/5V"))
    )
    (comp (ref "R57")
      (value "220")
      (footprint "eagle-import:0207_5V")
      (libsource (lib "eagle-import") (part "R-EU_0207/5V"))
    )
    (comp (ref "R58")
      (value "220")
      (footprint "eagle-import:0207_5V")
      (libsource (lib "eagle-import") (part "R-EU_0207/5V"))
    )
    (comp (ref "R59")
      (value "470")
      (footprint "eagle-import:0207_5V")
      (libsource (lib "eagle-import") (part "R-EU_0207/5V"))
    )
    (comp (ref "R63")
      (value "4K7")
      (footprint "eagle-import:0207_12")
      (libsource (lib "eagle-import") (part "R-EU_0207/12"))
    )
    (comp (ref "R64")
      (value "4K7")
      (footprint "eagle-import:0207_12")
      (libsource (lib "eagle-import") (part "R-EU_0207/12"))
    )
    (comp (ref "R65")
      (value "1K")
      (footprint "eagle-import:0207_12")
      (libsource (lib "eagle-import") (part "R-EU_0207/12"))
    )
    (comp (ref "R66")
      (value "470")
      (footprint "eagle-import:0207_12")
      (libsource (lib "eagle-import") (part "R-EU_0207/12"))
    )
    (comp (ref "R67")
      (value "470")
      (footprint "eagle-import:0207_12")
      (libsource (lib "eagle-import") (part "R-EU_0207/12"))
    )
    (comp (ref "R68")
      (value "100")
      (footprint "eagle-import:0207_12")
      (libsource (lib "eagle-import") (part "R-EU_0207/12"))
    )
    (comp (ref "R69")
      (value "100")
      (footprint "eagle-import:0207_5V")
      (libsource (lib "eagle-import") (part "R-EU_0207/5V"))
    )
    (comp (ref "R70")
      (value "100")
      (footprint "eagle-import:0207_5V")
      (libsource (lib "eagle-import") (part "R-EU_0207/5V"))
    )
    (comp (ref "R71")
      (value "3K3")
      (footprint "eagle-import:0207_5V")
      (libsource (lib "eagle-import") (part "R-EU_0207/5V"))
    )
    (comp (ref "R72")
      (value "10K")
      (footprint "eagle-import:0207_5V")
      (libsource (lib "eagle-import") (part "R-EU_0207/5V"))
    )
    (comp (ref "R73")
      (value "10K")
      (footprint "eagle-import:0207_5V")
      (libsource (lib "eagle-import") (part "R-EU_0207/5V"))
    )
    (comp (ref "R73_")
      (value "3K3")
      (footprint "eagle-import:0207_12")
      (libsource (lib "eagle-import") (part "R-EU_0207/12"))
    )
    (comp (ref "R74")
      (value "10K")
      (footprint "eagle-import:0207_5V")
      (libsource (lib "eagle-import") (part "R-EU_0207/5V"))
    )
    (comp (ref "R74_")
      (value "470")
      (footprint "eagle-import:0207_12")
      (libsource (lib "eagle-import") (part "R-EU_0207/12"))
    )
    (comp (ref "R75")
      (value "10K")
      (footprint "eagle-import:0207_12")
      (libsource (lib "eagle-import") (part "R-EU_0207/12"))
    )
    (comp (ref "R76")
      (value "75")
      (footprint "eagle-import:0207_5V")
      (libsource (lib "eagle-import") (part "R-EU_0207/5V"))
    )
    (comp (ref "TP1")
      (value "TPSQPAD1-13")
      (footprint "eagle-import:P1-13")
      (libsource (lib "eagle-import") (part "TPSQPAD1-13"))
    )
    (comp (ref "TP2")
      (value "TPSQPAD1-13")
      (footprint "eagle-import:P1-13")
      (libsource (lib "eagle-import") (part "TPSQPAD1-13"))
    )
    (comp (ref "TP3")
      (value "TPSQPAD1-13")
      (footprint "eagle-import:P1-13")
      (libsource (lib "eagle-import") (part "TPSQPAD1-13"))
    )
    (comp (ref "TP4")
      (value "TPSQPAD1-13")
      (footprint "eagle-import:P1-13")
      (libsource (lib "eagle-import") (part "TPSQPAD1-13"))
    )
    (comp (ref "TP5")
      (value "TPSQPAD1-13")
      (footprint "eagle-import:P1-13")
      (libsource (lib "eagle-import") (part "TPSQPAD1-13"))
    )
    (comp (ref "TP6")
      (value "TPSQPAD1-13")
      (footprint "eagle-import:P1-13")
      (libsource (lib "eagle-import") (part "TPSQPAD1-13"))
    )
    (comp (ref "TP7")
      (value "TPSQPAD1-13")
      (footprint "eagle-import:P1-13")
      (libsource (lib "eagle-import") (part "TPSQPAD1-13"))
    )
    (comp (ref "TP8")
      (value "TPSQPAD1-13")
      (footprint "eagle-import:P1-13")
      (libsource (lib "eagle-import") (part "TPSQPAD1-13"))
    )
    (comp (ref "TP9")
      (value "TPSQPAD1-13")
      (footprint "eagle-import:P1-13")
      (libsource (lib "eagle-import") (part "TPSQPAD1-13"))
    )
    (comp (ref "TP10")
      (value "TPSQPAD1-13")
      (footprint "eagle-import:P1-13")
      (libsource (lib "eagle-import") (part "TPSQPAD1-13"))
    )
    (comp (ref "U$1")
      (value "TK90_EDGE")
      (footprint "eagle-import:TK-EDGE")
      (libsource (lib "eagle-import") (part "TK90_EDGE"))
    )
    (comp (ref "X1")
      (value "RCA2PINA1")
      (footprint "eagle-import:TOBU3")
      (fields (field (name "MF") "FARNELL") (field (name "MPN") "TOBU 3"))
      (libsource (lib "eagle-import") (part "RCA2PINA1"))
    )
    (comp (ref "X2")
      (value "POWER")
      (footprint "eagle-import:MONO")
      (libsource (lib "eagle-import") (part "JACK?-MONO"))
    )
    (comp (ref "XTAL")
      (value "14.3044MHz")
      (footprint "eagle-import:HC49_S")
      (libsource (lib "eagle-import") (part "CRYSTALHC49S"))
    )
  )
  (nets
    (net (code "1") (name "+5V") (class "Default")
      (node (ref "7805") (pin "OUT") (pinfunction "OUT_OUT") (pintype "passive"))
      (node (ref "C1") (pin "+") (pinfunction "+_+") (pintype "passive"))
      (node (ref "C12") (pin "2") (pinfunction "2_2") (pintype "passive"))
      (node (ref "C13") (pin "2") (pinfunction "2_2") (pintype "passive"))
      (node (ref "C14") (pin "2") (pinfunction "2_2") (pintype "passive"))
      (node (ref "C15") (pin "1") (pinfunction "1_1") (pintype "passive"))
      (node (ref "C16") (pin "1") (pinfunction "1_1") (pintype "passive"))
      (node (ref "C18") (pin "1") (pinfunction "1_1") (pintype "passive"))
      (node (ref "C19") (pin "1") (pinfunction "1_1") (pintype "passive"))
      (node (ref "C20") (pin "1") (pinfunction "1_1") (pintype "passive"))
      (node (ref "C21") (pin "1") (pinfunction "1_1") (pintype "passive"))
      (node (ref "C22") (pin "2") (pinfunction "2_2") (pintype "passive"))
      (node (ref "C24") (pin "2") (pinfunction "2_2") (pintype "passive"))
      (node (ref "C29") (pin "2") (pinfunction "2_2") (pintype "passive"))
      (node (ref "C31") (pin "2") (pinfunction "2_2") (pintype "passive"))
      (node (ref "C32") (pin "2") (pinfunction "2_2") (pintype "passive"))
      (node (ref "C33") (pin "2") (pinfunction "2_2") (pintype "passive"))
      (node (ref "D13") (pin "C") (pinfunction "K_C") (pintype "bidirectional"))
      (node (ref "D15") (pin "C") (pinfunction "K_C") (pintype "bidirectional"))
      (node (ref "D17") (pin "C") (pinfunction "K_C") (pintype "bidirectional"))
      (node (ref "IC1") (pin "11") (pinfunction "VCC_11") (pintype "power_in"))
      (node (ref "IC10") (pin "16") (pinfunction "VCC_16") (pintype "power_in"))
      (node (ref "IC11") (pin "20") (pinfunction "VCC_20") (pintype "power_in"))
      (node (ref "IC12") (pin "3") (pinfunction "CR_BIAS_3") (pintype "input"))
      (node (ref "IC13") (pin "9") (pinfunction "A7_9") (pintype "input"))
      (node (ref "IC14") (pin "9") (pinfunction "A7_9") (pintype "input"))
      (node (ref "IC15") (pin "9") (pinfunction "A7_9") (pintype "input"))
      (node (ref "IC16") (pin "9") (pinfunction "A7_9") (pintype "input"))
      (node (ref "IC17") (pin "9") (pinfunction "A7_9") (pintype "input"))
      (node (ref "IC18") (pin "9") (pinfunction "A7_9") (pintype "input"))
      (node (ref "IC19") (pin "9") (pinfunction "A7_9") (pintype "input"))
      (node (ref "IC2") (pin "1") (pinfunction "VPP_1") (pintype "input"))
      (node (ref "IC2") (pin "28") (pinfunction "VCC_28") (pintype "power_in"))
      (node (ref "IC20") (pin "9") (pinfunction "A7_9") (pintype "input"))
      (node (ref "IC21") (pin "9") (pinfunction "VCC_9") (pintype "power_in"))
      (node (ref "IC22") (pin "9") (pinfunction "VCC_9") (pintype "power_in"))
      (node (ref "IC23") (pin "9") (pinfunction "VCC_9") (pintype "power_in"))
      (node (ref "IC24") (pin "9") (pinfunction "VCC_9") (pintype "power_in"))
      (node (ref "IC25") (pin "14") (pinfunction "VCC_14") (pintype "power_in"))
      (node (ref "IC26") (pin "1") (pinfunction "I0_1") (pintype "input"))
      (node (ref "IC26") (pin "14") (pinfunction "VCC_14") (pintype "power_in"))
      (node (ref "IC27") (pin "14") (pinfunction "VCC_14") (pintype "power_in"))
      (node (ref "IC28") (pin "14") (pinfunction "VCC_14") (pintype "power_in"))
      (node (ref "IC3") (pin "40") (pinfunction "VCC_40") (pintype "power_in"))
      (node (ref "IC4") (pin "10") (pinfunction "PRE_10") (pintype "input"))
      (node (ref "IC4") (pin "13") (pinfunction "CLR_13") (pintype "input"))
      (node (ref "IC4") (pin "14") (pinfunction "VCC_14") (pintype "power_in"))
      (node (ref "IC5") (pin "1") (pinfunction "CLR_1") (pintype "input"))
      (node (ref "IC5") (pin "10") (pinfunction "PRE_10") (pintype "input"))
      (node (ref "IC5") (pin "13") (pinfunction "CLR_13") (pintype "input"))
      (node (ref "IC5") (pin "14") (pinfunction "VCC_14") (pintype "power_in"))
      (node (ref "IC5") (pin "4") (pinfunction "PRE_4") (pintype "input"))
      (node (ref "IC6") (pin "16") (pinfunction "VCC_16") (pintype "power_in"))
      (node (ref "IC7") (pin "16") (pinfunction "VCC_16") (pintype "power_in"))
      (node (ref "IC8") (pin "16") (pinfunction "VCC_16") (pintype "power_in"))
      (node (ref "IC9") (pin "16") (pinfunction "VCC_16") (pintype "power_in"))
      (node (ref "JP2") (pin "1") (pinfunction "1_1") (pintype "passive"))
      (node (ref "Q1") (pin "3") (pinfunction "C_3") (pintype "passive"))
      (node (ref "Q8") (pin "C") (pinfunction "C_C") (pintype "passive"))
      (node (ref "R17") (pin "2") (pinfunction "2_2") (pintype "passive"))
      (node (ref "R18") (pin "2") (pinfunction "2_2") (pintype "passive"))
      (node (ref "R19") (pin "2") (pinfunction "2_2") (pintype "passive"))
      (node (ref "R20") (pin "2") (pinfunction "2_2") (pintype "passive"))
      (node (ref "R21") (pin "2") (pinfunction "2_2") (pintype "passive"))
      (node (ref "R22") (pin "2") (pinfunction "2_2") (pintype "passive"))
      (node (ref "R23") (pin "2") (pinfunction "2_2") (pintype "passive"))
      (node (ref "R24") (pin "2") (pinfunction "2_2") (pintype "passive"))
      (node (ref "R29") (pin "2") (pinfunction "2_2") (pintype "passive"))
      (node (ref "R30") (pin "1") (pinfunction "1_1") (pintype "passive"))
      (node (ref "R31") (pin "1") (pinfunction "1_1") (pintype "passive"))
      (node (ref "R32") (pin "1") (pinfunction "1_1") (pintype "passive"))
      (node (ref "R35") (pin "1") (pinfunction "1_1") (pintype "passive"))
      (node (ref "R36") (pin "1") (pinfunction "1_1") (pintype "passive"))
      (node (ref "R37") (pin "1") (pinfunction "1_1") (pintype "passive"))
      (node (ref "R38") (pin "1") (pinfunction "1_1") (pintype "passive"))
      (node (ref "R39") (pin "1") (pinfunction "1_1") (pintype "passive"))
      (node (ref "R40") (pin "2") (pinfunction "2_2") (pintype "passive"))
      (node (ref "R43") (pin "2") (pinfunction "2_2") (pintype "passive"))
      (node (ref "R48") (pin "2") (pinfunction "2_2") (pintype "passive"))
      (node (ref "R51") (pin "2") (pinfunction "2_2") (pintype "passive"))
      (node (ref "R74_") (pin "2") (pinfunction "2_2") (pintype "passive"))
      (node (ref "U$1") (pin "3A") (pinfunction "EDGE_3A") (pintype "bidirectional"))
    )
    (net (code "2") (name "+12V") (class "Default")
      (node (ref "C43") (pin "2") (pinfunction "2_2") (pintype "passive"))
      (node (ref "C53") (pin "+") (pinfunction "+_+") (pintype "passive"))
      (node (ref "D24") (pin "C") (pinfunction "K_C") (pintype "bidirectional"))
      (node (ref "IC11") (pin "5") (pinfunction "+12V_5") (pintype "power_in"))
      (node (ref "IC12") (pin "14") (pinfunction "RFVCC_14") (pintype "power_in"))
      (node (ref "IC12") (pin "16") (pinfunction "CRVCC_16") (pintype "power_in"))
      (node (ref "L1") (pin "2") (pinfunction "A_2") (pintype "passive"))
      (node (ref "R54") (pin "1") (pinfunction "1_1") (pintype "passive"))
      (node (ref "R57") (pin "1") (pinfunction "1_1") (pintype "passive"))
      (node (ref "R58") (pin "1") (pinfunction "1_1") (pintype "passive"))
      (node (ref "R59") (pin "1") (pinfunction "1_1") (pintype "passive"))
      (node (ref "R68") (pin "1") (pinfunction "1_1") (pintype "passive"))
      (node (ref "U$1") (pin "22B") (pinfunction "EDGE_22B") (pintype "bidirectional"))
    )
    (net (code "3") (name "-5V") (class "Default")
      (node (ref "C50") (pin "1") (pinfunction "1_1") (pintype "passive"))
      (node (ref "D21") (pin "A") (pinfunction "A_A") (pintype "bidirectional"))
      (node (ref "J3") (pin "1") (pinfunction "1_1") (pintype "passive"))
      (node (ref "R67") (pin "1") (pinfunction "1_1") (pintype "passive"))
      (node (ref "U$1") (pin "20B") (pinfunction "EDGE_20B") (pintype "bidirectional"))
    )
    (net (code "4") (name "/+12V_UNREG") (class "Default")
      (node (ref "C48") (pin "1") (pinfunction "1_1") (pintype "passive"))
      (node (ref "C51") (pin "1") (pinfunction "1_1") (pintype "passive"))
      (node (ref "Q5") (pin "E") (pinfunction "E_E") (pintype "passive"))
      (node (ref "Q6") (pin "E") (pinfunction "E_E") (pintype "passive"))
      (node (ref "U$1") (pin "23B") (pinfunction "EDGE_23B") (pintype "bidirectional"))
    )
    (net (code "5") (name "/A0") (class "Default")
      (node (ref "IC1") (pin "30") (pinfunction "A0_30") (pintype "output"))
      (node (ref "IC2") (pin "10") (pinfunction "A0_10") (pintype "input"))
      (node (ref "IC7") (pin "3") (pinfunction "1B_3") (pintype "input"))
      (node (ref "IC8") (pin "3") (pinfunction "1B_3") (pintype "input"))
      (node (ref "Q1") (pin "2") (pinfunction "B_2") (pintype "passive"))
      (node (ref "U$1") (pin "9A") (pinfunction "EDGE_9A") (pintype "bidirectional"))
    )
    (net (code "6") (name "/A1") (class "Default")
      (node (ref "IC1") (pin "31") (pinfunction "A1_31") (pintype "output"))
      (node (ref "IC2") (pin "9") (pinfunction "A1_9") (pintype "input"))
      (node (ref "IC7") (pin "6") (pinfunction "2B_6") (pintype "input"))
      (node (ref "IC8") (pin "6") (pinfunction "2B_6") (pintype "input"))
      (node (ref "U$1") (pin "10A") (pinfunction "EDGE_10A") (pintype "bidirectional"))
    )
    (net (code "7") (name "/A2") (class "Default")
      (node (ref "IC1") (pin "32") (pinfunction "A2_32") (pintype "output"))
      (node (ref "IC2") (pin "8") (pinfunction "A2_8") (pintype "input"))
      (node (ref "IC7") (pin "13") (pinfunction "4B_13") (pintype "input"))
      (node (ref "IC8") (pin "13") (pinfunction "4B_13") (pintype "input"))
      (node (ref "U$1") (pin "11A") (pinfunction "EDGE_11A") (pintype "bidirectional"))
    )
    (net (code "8") (name "/A3") (class "Default")
      (node (ref "IC1") (pin "33") (pinfunction "A3_33") (pintype "output"))
      (node (ref "IC2") (pin "7") (pinfunction "A3_7") (pintype "input"))
      (node (ref "IC7") (pin "10") (pinfunction "3B_10") (pintype "input"))
      (node (ref "IC8") (pin "10") (pinfunction "3B_10") (pintype "input"))
      (node (ref "U$1") (pin "12A") (pinfunction "EDGE_12A") (pintype "bidirectional"))
    )
    (net (code "9") (name "/A4") (class "Default")
      (node (ref "IC1") (pin "34") (pinfunction "A4_34") (pintype "output"))
      (node (ref "IC2") (pin "6") (pinfunction "A4_6") (pintype "input"))
      (node (ref "IC6") (pin "6") (pinfunction "2B_6") (pintype "input"))
      (node (ref "IC9") (pin "6") (pinfunction "2B_6") (pintype "input"))
      (node (ref "U$1") (pin "24A") (pinfunction "EDGE_24A") (pintype "bidirectional"))
    )
    (net (code "10") (name "/A5") (class "Default")
      (node (ref "IC1") (pin "35") (pinfunction "A5_35") (pintype "output"))
      (node (ref "IC2") (pin "5") (pinfunction "A5_5") (pintype "input"))
      (node (ref "IC6") (pin "13") (pinfunction "4B_13") (pintype "input"))
      (node (ref "IC9") (pin "13") (pinfunction "4B_13") (pintype "input"))
      (node (ref "U$1") (pin "23A") (pinfunction "EDGE_23A") (pintype "bidirectional"))
    )
    (net (code "11") (name "/A6") (class "Default")
      (node (ref "IC1") (pin "36") (pinfunction "A6_36") (pintype "output"))
      (node (ref "IC2") (pin "4") (pinfunction "A6_4") (pintype "input"))
      (node (ref "IC21") (pin "14") (pinfunction "A0_14") (pintype "input"))
      (node (ref "IC22") (pin "14") (pinfunction "A0_14") (pintype "input"))
      (node (ref "IC23") (pin "14") (pinfunction "A0_14") (pintype "input"))
      (node (ref "IC24") (pin "14") (pinfunction "A0_14") (pintype "input"))
      (node (ref "IC5") (pin "12") (pinfunction "D_12") (pintype "input"))
      (node (ref "IC9") (pin "10") (pinfunction "3B_10") (pintype "input"))
      (node (ref "U$1") (pin "22A") (pinfunction "EDGE_22A") (pintype "bidirectional"))
    )
    (net (code "12") (name "/A7") (class "Default")
      (node (ref "IC1") (pin "37") (pinfunction "A7_37") (pintype "output"))
      (node (ref "IC2") (pin "3") (pinfunction "A7_3") (pintype "input"))
      (node (ref "IC26") (pin "12") (pinfunction "I0_12") (pintype "input"))
      (node (ref "IC8") (pin "2") (pinfunction "1A_2") (pintype "input"))
      (node (ref "U$1") (pin "21A") (pinfunction "EDGE_21A") (pintype "bidirectional"))
    )
    (net (code "13") (name "/A7'") (class "Default")
      (node (ref "IC21") (pin "10") (pinfunction "A7_10") (pintype "input"))
      (node (ref "IC22") (pin "10") (pinfunction "A7_10") (pintype "input"))
      (node (ref "IC23") (pin "10") (pinfunction "A7_10") (pintype "input"))
      (node (ref "IC24") (pin "10") (pinfunction "A7_10") (pintype "input"))
      (node (ref "IC26") (pin "8") (pinfunction "O_8") (pintype "output"))
    )
    (net (code "14") (name "/A8") (class "Default")
      (node (ref "D2") (pin "C") (pinfunction "K_C") (pintype "bidirectional"))
      (node (ref "IC1") (pin "38") (pinfunction "A8_38") (pintype "output"))
      (node (ref "IC2") (pin "25") (pinfunction "A8_25") (pintype "input"))
      (node (ref "IC7") (pin "5") (pinfunction "2A_5") (pintype "input"))
      (node (ref "IC8") (pin "5") (pinfunction "2A_5") (pintype "input"))
      (node (ref "U$1") (pin "26B") (pinfunction "EDGE_26B") (pintype "bidirectional"))
    )
    (net (code "15") (name "/A8-1") (class "Default")
      (node (ref "IC21") (pin "7") (pinfunction "A5_7") (pintype "input"))
      (node (ref "IC22") (pin "7") (pinfunction "A5_7") (pintype "input"))
      (node (ref "IC23") (pin "7") (pinfunction "A5_7") (pintype "input"))
      (node (ref "IC24") (pin "7") (pinfunction "A5_7") (pintype "input"))
      (node (ref "IC7") (pin "7") (pinfunction "2Y_7") (pintype "output"))
    )
    (net (code "16") (name "/A9") (class "Default")
      (node (ref "D3") (pin "C") (pinfunction "K_C") (pintype "bidirectional"))
      (node (ref "IC1") (pin "39") (pinfunction "A9_39") (pintype "output"))
      (node (ref "IC2") (pin "24") (pinfunction "A9_24") (pintype "input"))
      (node (ref "IC7") (pin "14") (pinfunction "4A_14") (pintype "input"))
      (node (ref "IC8") (pin "14") (pinfunction "4A_14") (pintype "input"))
      (node (ref "U$1") (pin "27A") (pinfunction "EDGE_27A") (pintype "bidirectional"))
    )
    (net (code "17") (name "/A9-2") (class "Default")
      (node (ref "IC21") (pin "8") (pinfunction "A4_8") (pintype "input"))
      (node (ref "IC22") (pin "8") (pinfunction "A4_8") (pintype "input"))
      (node (ref "IC23") (pin "8") (pinfunction "A4_8") (pintype "input"))
      (node (ref "IC24") (pin "8") (pinfunction "A4_8") (pintype "input"))
      (node (ref "IC7") (pin "12") (pinfunction "4Y_12") (pintype "output"))
    )
    (net (code "18") (name "/A10") (class "Default")
      (node (ref "D4") (pin "C") (pinfunction "K_C") (pintype "bidirectional"))
      (node (ref "IC1") (pin "40") (pinfunction "A10_40") (pintype "output"))
      (node (ref "IC2") (pin "21") (pinfunction "A10_21") (pintype "input"))
      (node (ref "IC7") (pin "11") (pinfunction "3A_11") (pintype "input"))
      (node (ref "IC8") (pin "11") (pinfunction "3A_11") (pintype "input"))
      (node (ref "U$1") (pin "27B") (pinfunction "EDGE_27B") (pintype "bidirectional"))
    )
    (net (code "19") (name "/A10-3") (class "Default")
      (node (ref "IC21") (pin "11") (pinfunction "A3_11") (pintype "input"))
      (node (ref "IC22") (pin "11") (pinfunction "A3_11") (pintype "input"))
      (node (ref "IC23") (pin "11") (pinfunction "A3_11") (pintype "input"))
      (node (ref "IC24") (pin "11") (pinfunction "A3_11") (pintype "input"))
      (node (ref "IC7") (pin "9") (pinfunction "3Y_9") (pintype "output"))
    )
    (net (code "20") (name "/A11") (class "Default")
      (node (ref "D5") (pin "C") (pinfunction "K_C") (pintype "bidirectional"))
      (node (ref "IC1") (pin "1") (pinfunction "A11_1") (pintype "output"))
      (node (ref "IC2") (pin "23") (pinfunction "A11_23") (pintype "input"))
      (node (ref "IC6") (pin "5") (pinfunction "2A_5") (pintype "input"))
      (node (ref "IC9") (pin "5") (pinfunction "2A_5") (pintype "input"))
      (node (ref "U$1") (pin "28A") (pinfunction "EDGE_28A") (pintype "bidirectional"))
    )
    (net (code "21") (name "/A11-4") (class "Default")
      (node (ref "IC21") (pin "12") (pinfunction "A2_12") (pintype "input"))
      (node (ref "IC22") (pin "12") (pinfunction "A2_12") (pintype "input"))
      (node (ref "IC23") (pin "12") (pinfunction "A2_12") (pintype "input"))
      (node (ref "IC24") (pin "12") (pinfunction "A2_12") (pintype "input"))
      (node (ref "IC6") (pin "7") (pinfunction "2Y_7") (pintype "output"))
    )
    (net (code "22") (name "/A12") (class "Default")
      (node (ref "D6") (pin "C") (pinfunction "K_C") (pintype "bidirectional"))
      (node (ref "IC1") (pin "2") (pinfunction "A12_2") (pintype "output"))
      (node (ref "IC2") (pin "2") (pinfunction "A12_2") (pintype "input"))
      (node (ref "IC6") (pin "14") (pinfunction "4A_14") (pintype "input"))
      (node (ref "IC9") (pin "14") (pinfunction "4A_14") (pintype "input"))
      (node (ref "U$1") (pin "2A") (pinfunction "EDGE_2A") (pintype "bidirectional"))
    )
    (net (code "23") (name "/A12-5") (class "Default")
      (node (ref "IC21") (pin "13") (pinfunction "A1_13") (pintype "input"))
      (node (ref "IC22") (pin "13") (pinfunction "A1_13") (pintype "input"))
      (node (ref "IC23") (pin "13") (pinfunction "A1_13") (pintype "input"))
      (node (ref "IC24") (pin "13") (pinfunction "A1_13") (pintype "input"))
      (node (ref "IC6") (pin "12") (pinfunction "4Y_12") (pintype "output"))
    )
    (net (code "24") (name "/A13") (class "Default")
      (node (ref "D7") (pin "C") (pinfunction "K_C") (pintype "bidirectional"))
      (node (ref "IC1") (pin "3") (pinfunction "A13_3") (pintype "output"))
      (node (ref "IC2") (pin "26") (pinfunction "A13_26") (pintype "input"))
      (node (ref "IC7") (pin "2") (pinfunction "1A_2") (pintype "input"))
      (node (ref "IC9") (pin "11") (pinfunction "3A_11") (pintype "input"))
      (node (ref "U$1") (pin "2B") (pinfunction "EDGE_2B") (pintype "bidirectional"))
    )
    (net (code "25") (name "/A13-0") (class "Default")
      (node (ref "IC21") (pin "6") (pinfunction "A6_6") (pintype "input"))
      (node (ref "IC22") (pin "6") (pinfunction "A6_6") (pintype "input"))
      (node (ref "IC23") (pin "6") (pinfunction "A6_6") (pintype "input"))
      (node (ref "IC24") (pin "6") (pinfunction "A6_6") (pintype "input"))
      (node (ref "IC7") (pin "4") (pinfunction "1Y_4") (pintype "output"))
    )
    (net (code "26") (name "/A14") (class "Default")
      (node (ref "D12") (pin "A") (pinfunction "A_A") (pintype "bidirectional"))
      (node (ref "D8") (pin "C") (pinfunction "K_C") (pintype "bidirectional"))
      (node (ref "IC1") (pin "4") (pinfunction "A14_4") (pintype "output"))
      (node (ref "IC25") (pin "4") (pinfunction "I0_4") (pintype "input"))
      (node (ref "IC27") (pin "12") (pinfunction "I0_12") (pintype "input"))
      (node (ref "IC28") (pin "1") (pinfunction "I_1") (pintype "input"))
      (node (ref "IC3") (pin "37") (pinfunction "A14_37") (pintype "input"))
      (node (ref "U$1") (pin "1A") (pinfunction "EDGE_1A") (pintype "bidirectional"))
    )
    (net (code "27") (name "/A15") (class "Default")
      (node (ref "D11") (pin "A") (pinfunction "A_A") (pintype "bidirectional"))
      (node (ref "D9") (pin "C") (pinfunction "K_C") (pintype "bidirectional"))
      (node (ref "IC1") (pin "5") (pinfunction "A15_5") (pintype "output"))
      (node (ref "IC25") (pin "13") (pinfunction "I1_13") (pintype "input"))
      (node (ref "IC27") (pin "13") (pinfunction "I1_13") (pintype "input"))
      (node (ref "IC3") (pin "38") (pinfunction "A15_38") (pintype "input"))
      (node (ref "U$1") (pin "1B") (pinfunction "EDGE_1B") (pintype "bidirectional"))
    )
    (net (code "28") (name "/AA0") (class "Default")
      (node (ref "IC13") (pin "5") (pinfunction "A0_5") (pintype "input"))
      (node (ref "IC14") (pin "5") (pinfunction "A0_5") (pintype "input"))
      (node (ref "IC15") (pin "5") (pinfunction "A0_5") (pintype "input"))
      (node (ref "IC16") (pin "5") (pinfunction "A0_5") (pintype "input"))
      (node (ref "IC17") (pin "5") (pinfunction "A0_5") (pintype "input"))
      (node (ref "IC18") (pin "5") (pinfunction "A0_5") (pintype "input"))
      (node (ref "IC19") (pin "5") (pinfunction "A0_5") (pintype "input"))
      (node (ref "IC20") (pin "5") (pinfunction "A0_5") (pintype "input"))
      (node (ref "IC3") (pin "9") (pinfunction "A0_9") (pintype "output"))
      (node (ref "R9") (pin "1") (pinfunction "1_1") (pintype "passive"))
    )
    (net (code "29") (name "/AA1") (class "Default")
      (node (ref "IC13") (pin "7") (pinfunction "A1_7") (pintype "input"))
      (node (ref "IC14") (pin "7") (pinfunction "A1_7") (pintype "input"))
      (node (ref "IC15") (pin "7") (pinfunction "A1_7") (pintype "input"))
      (node (ref "IC16") (pin "7") (pinfunction "A1_7") (pintype "input"))
      (node (ref "IC17") (pin "7") (pinfunction "A1_7") (pintype "input"))
      (node (ref "IC18") (pin "7") (pinfunction "A1_7") (pintype "input"))
      (node (ref "IC19") (pin "7") (pinfunction "A1_7") (pintype "input"))
      (node (ref "IC20") (pin "7") (pinfunction "A1_7") (pintype "input"))
      (node (ref "IC3") (pin "7") (pinfunction "A1_7") (pintype "output"))
      (node (ref "R11") (pin "1") (pinfunction "1_1") (pintype "passive"))
    )
    (net (code "30") (name "/AA2") (class "Default")
      (node (ref "IC13") (pin "6") (pinfunction "A2_6") (pintype "input"))
      (node (ref "IC14") (pin "6") (pinfunction "A2_6") (pintype "input"))
      (node (ref "IC15") (pin "6") (pinfunction "A2_6") (pintype "input"))
      (node (ref "IC16") (pin "6") (pinfunction "A2_6") (pintype "input"))
      (node (ref "IC17") (pin "6") (pinfunction "A2_6") (pintype "input"))
      (node (ref "IC18") (pin "6") (pinfunction "A2_6") (pintype "input"))
      (node (ref "IC19") (pin "6") (pinfunction "A2_6") (pintype "input"))
      (node (ref "IC20") (pin "6") (pinfunction "A2_6") (pintype "input"))
      (node (ref "IC3") (pin "8") (pinfunction "A2_8") (pintype "output"))
      (node (ref "R10") (pin "1") (pinfunction "1_1") (pintype "passive"))
    )
    (net (code "31") (name "/AA3") (class "Default")
      (node (ref "IC13") (pin "12") (pinfunction "A3_12") (pintype "input"))
      (node (ref "IC14") (pin "12") (pinfunction "A3_12") (pintype "input"))
      (node (ref "IC15") (pin "12") (pinfunction "A3_12") (pintype "input"))
      (node (ref "IC16") (pin "12") (pinfunction "A3_12") (pintype "input"))
      (node (ref "IC17") (pin "12") (pinfunction "A3_12") (pintype "input"))
      (node (ref "IC18") (pin "12") (pinfunction "A3_12") (pintype "input"))
      (node (ref "IC19") (pin "12") (pinfunction "A3_12") (pintype "input"))
      (node (ref "IC20") (pin "12") (pinfunction "A3_12") (pintype "input"))
      (node (ref "IC3") (pin "4") (pinfunction "A3_4") (pintype "output"))
      (node (ref "R14") (pin "1") (pinfunction "1_1") (pintype "passive"))
    )
    (net (code "32") (name "/AA4") (class "Default")
      (node (ref "IC13") (pin "11") (pinfunction "A4_11") (pintype "input"))
      (node (ref "IC14") (pin "11") (pinfunction "A4_11") (pintype "input"))
      (node (ref "IC15") (pin "11") (pinfunction "A4_11") (pintype "input"))
      (node (ref "IC16") (pin "11") (pinfunction "A4_11") (pintype "input"))
      (node (ref "IC17") (pin "11") (pinfunction "A4_11") (pintype "input"))
      (node (ref "IC18") (pin "11") (pinfunction "A4_11") (pintype "input"))
      (node (ref "IC19") (pin "11") (pinfunction "A4_11") (pintype "input"))
      (node (ref "IC20") (pin "11") (pinfunction "A4_11") (pintype "input"))
      (node (ref "IC3") (pin "5") (pinfunction "A4_5") (pintype "output"))
      (node (ref "R13") (pin "1") (pinfunction "1_1") (pintype "passive"))
    )
    (net (code "33") (name "/AA5") (class "Default")
      (node (ref "IC13") (pin "10") (pinfunction "A5_10") (pintype "input"))
      (node (ref "IC14") (pin "10") (pinfunction "A5_10") (pintype "input"))
      (node (ref "IC15") (pin "10") (pinfunction "A5_10") (pintype "input"))
      (node (ref "IC16") (pin "10") (pinfunction "A5_10") (pintype "input"))
      (node (ref "IC17") (pin "10") (pinfunction "A5_10") (pintype "input"))
      (node (ref "IC18") (pin "10") (pinfunction "A5_10") (pintype "input"))
      (node (ref "IC19") (pin "10") (pinfunction "A5_10") (pintype "input"))
      (node (ref "IC20") (pin "10") (pinfunction "A5_10") (pintype "input"))
      (node (ref "IC3") (pin "6") (pinfunction "A5_6") (pintype "output"))
      (node (ref "R12") (pin "1") (pinfunction "1_1") (pintype "passive"))
    )
    (net (code "34") (name "/AA6") (class "Default")
      (node (ref "IC13") (pin "13") (pinfunction "A6_13") (pintype "input"))
      (node (ref "IC14") (pin "13") (pinfunction "A6_13") (pintype "input"))
      (node (ref "IC15") (pin "13") (pinfunction "A6_13") (pintype "input"))
      (node (ref "IC16") (pin "13") (pinfunction "A6_13") (pintype "input"))
      (node (ref "IC17") (pin "13") (pinfunction "A6_13") (pintype "input"))
      (node (ref "IC18") (pin "13") (pinfunction "A6_13") (pintype "input"))
      (node (ref "IC19") (pin "13") (pinfunction "A6_13") (pintype "input"))
      (node (ref "IC20") (pin "13") (pinfunction "A6_13") (pintype "input"))
      (node (ref "IC3") (pin "3") (pinfunction "A6_3") (pintype "output"))
      (node (ref "R15") (pin "1") (pinfunction "1_1") (pintype "passive"))
    )
    (net (code "35") (name "/CARRIER") (class "Default")
      (node (ref "C47") (pin "1") (pinfunction "1_1") (pintype "passive"))
      (node (ref "D17") (pin "A") (pinfunction "A_A") (pintype "bidirectional"))
      (node (ref "D18") (pin "C") (pinfunction "K_C") (pintype "bidirectional"))
      (node (ref "IC3") (pin "39") (pinfunction "CARRIER_39") (pintype "output"))
      (node (ref "R64") (pin "2") (pinfunction "2_2") (pintype "passive"))
      (node (ref "R71") (pin "2") (pinfunction "2_2") (pintype "passive"))
    )
    (net (code "36") (name "/CLK") (class "Default")
      (node (ref "C9") (pin "2") (pinfunction "2_2") (pintype "passive"))
      (node (ref "IC3") (pin "36") (pinfunction "CKOUT_36") (pintype "output"))
      (node (ref "R49") (pin "2") (pinfunction "2_2") (pintype "passive"))
      (node (ref "R51") (pin "1") (pinfunction "1_1") (pintype "passive"))
      (node (ref "U$1") (pin "8A") (pinfunction "EDGE_8A") (pintype "bidirectional"))
    )
    (net (code "37") (name "/D0") (class "Default")
      (node (ref "IC1") (pin "14") (pinfunction "D0_14") (pintype "bidirectional"))
      (node (ref "IC10") (pin "3") (pinfunction "Y1_3") (pintype "tri_state"))
      (node (ref "IC2") (pin "11") (pinfunction "O0_11") (pintype "tri_state"))
      (node (ref "IC21") (pin "2") (pinfunction "I/O1_2") (pintype "bidirectional"))
      (node (ref "IC23") (pin "2") (pinfunction "I/O1_2") (pintype "bidirectional"))
      (node (ref "R1") (pin "2") (pinfunction "2_2") (pintype "passive"))
      (node (ref "R17") (pin "1") (pinfunction "1_1") (pintype "passive"))
      (node (ref "U$1") (pin "6B") (pinfunction "EDGE_6B") (pintype "bidirectional"))
    )
    (net (code "38") (name "/D0'") (class "Default")
      (node (ref "IC20") (pin "14") (pinfunction "DO_14") (pintype "bidirectional"))
      (node (ref "IC20") (pin "2") (pinfunction "DI_2") (pintype "bidirectional"))
      (node (ref "IC3") (pin "25") (pinfunction "D0_25") (pintype "bidirectional"))
      (node (ref "R1") (pin "1") (pinfunction "1_1") (pintype "passive"))
    )
    (net (code "39") (name "/D1") (class "Default")
      (node (ref "IC1") (pin "15") (pinfunction "D1_15") (pintype "bidirectional"))
      (node (ref "IC10") (pin "5") (pinfunction "Y2_5") (pintype "tri_state"))
      (node (ref "IC2") (pin "12") (pinfunction "O1_12") (pintype "tri_state"))
      (node (ref "IC21") (pin "3") (pinfunction "I/O2_3") (pintype "bidirectional"))
      (node (ref "IC23") (pin "3") (pinfunction "I/O2_3") (pintype "bidirectional"))
      (node (ref "R18") (pin "1") (pinfunction "1_1") (pintype "passive"))
      (node (ref "R2") (pin "2") (pinfunction "2_2") (pintype "passive"))
      (node (ref "U$1") (pin "7B") (pinfunction "EDGE_7B") (pintype "bidirectional"))
    )
    (net (code "40") (name "/D1'") (class "Default")
      (node (ref "IC19") (pin "14") (pinfunction "DO_14") (pintype "bidirectional"))
      (node (ref "IC19") (pin "2") (pinfunction "DI_2") (pintype "bidirectional"))
      (node (ref "IC3") (pin "26") (pinfunction "D1_26") (pintype "bidirectional"))
      (node (ref "R2") (pin "1") (pinfunction "1_1") (pintype "passive"))
    )
    (net (code "41") (name "/D2") (class "Default")
      (node (ref "IC1") (pin "12") (pinfunction "D2_12") (pintype "bidirectional"))
      (node (ref "IC10") (pin "7") (pinfunction "Y3_7") (pintype "tri_state"))
      (node (ref "IC2") (pin "13") (pinfunction "O2_13") (pintype "tri_state"))
      (node (ref "IC21") (pin "15") (pinfunction "I/O3_15") (pintype "bidirectional"))
      (node (ref "IC23") (pin "15") (pinfunction "I/O3_15") (pintype "bidirectional"))
      (node (ref "R19") (pin "1") (pinfunction "1_1") (pintype "passive"))
      (node (ref "R3") (pin "2") (pinfunction "2_2") (pintype "passive"))
      (node (ref "U$1") (pin "8B") (pinfunction "EDGE_8B") (pintype "bidirectional"))
    )
    (net (code "42") (name "/D2'") (class "Default")
      (node (ref "IC18") (pin "14") (pinfunction "DO_14") (pintype "bidirectional"))
      (node (ref "IC18") (pin "2") (pinfunction "DI_2") (pintype "bidirectional"))
      (node (ref "IC3") (pin "27") (pinfunction "D2_27") (pintype "bidirectional"))
      (node (ref "R3") (pin "1") (pinfunction "1_1") (pintype "passive"))
    )
    (net (code "43") (name "/D3") (class "Default")
      (node (ref "IC1") (pin "8") (pinfunction "D3_8") (pintype "bidirectional"))
      (node (ref "IC10") (pin "9") (pinfunction "Y4_9") (pintype "tri_state"))
      (node (ref "IC2") (pin "15") (pinfunction "O3_15") (pintype "tri_state"))
      (node (ref "IC21") (pin "17") (pinfunction "I/O4_17") (pintype "bidirectional"))
      (node (ref "IC23") (pin "17") (pinfunction "I/O4_17") (pintype "bidirectional"))
      (node (ref "R20") (pin "1") (pinfunction "1_1") (pintype "passive"))
      (node (ref "R4") (pin "2") (pinfunction "2_2") (pintype "passive"))
      (node (ref "U$1") (pin "11B") (pinfunction "EDGE_11B") (pintype "bidirectional"))
    )
    (net (code "44") (name "/D3'") (class "Default")
      (node (ref "IC17") (pin "14") (pinfunction "DO_14") (pintype "bidirectional"))
      (node (ref "IC17") (pin "2") (pinfunction "DI_2") (pintype "bidirectional"))
      (node (ref "IC3") (pin "28") (pinfunction "D3_28") (pintype "bidirectional"))
      (node (ref "R4") (pin "1") (pinfunction "1_1") (pintype "passive"))
    )
    (net (code "45") (name "/D4") (class "Default")
      (node (ref "IC1") (pin "7") (pinfunction "D4_7") (pintype "bidirectional"))
      (node (ref "IC10") (pin "11") (pinfunction "Y5_11") (pintype "tri_state"))
      (node (ref "IC2") (pin "16") (pinfunction "O4_16") (pintype "tri_state"))
      (node (ref "IC22") (pin "2") (pinfunction "I/O1_2") (pintype "bidirectional"))
      (node (ref "IC24") (pin "2") (pinfunction "I/O1_2") (pintype "bidirectional"))
      (node (ref "R21") (pin "1") (pinfunction "1_1") (pintype "passive"))
      (node (ref "R5") (pin "2") (pinfunction "2_2") (pintype "passive"))
      (node (ref "U$1") (pin "12B") (pinfunction "EDGE_12B") (pintype "bidirectional"))
    )
    (net (code "46") (name "/D4'") (class "Default")
      (node (ref "IC16") (pin "14") (pinfunction "DO_14") (pintype "bidirectional"))
      (node (ref "IC16") (pin "2") (pinfunction "DI_2") (pintype "bidirectional"))
      (node (ref "IC3") (pin "29") (pinfunction "D4_29") (pintype "bidirectional"))
      (node (ref "R5") (pin "1") (pinfunction "1_1") (pintype "passive"))
    )
    (net (code "47") (name "/D5") (class "Default")
      (node (ref "IC1") (pin "9") (pinfunction "D5_9") (pintype "bidirectional"))
      (node (ref "IC2") (pin "17") (pinfunction "O5_17") (pintype "tri_state"))
      (node (ref "IC22") (pin "3") (pinfunction "I/O2_3") (pintype "bidirectional"))
      (node (ref "IC24") (pin "3") (pinfunction "I/O2_3") (pintype "bidirectional"))
      (node (ref "R22") (pin "1") (pinfunction "1_1") (pintype "passive"))
      (node (ref "R6") (pin "2") (pinfunction "2_2") (pintype "passive"))
      (node (ref "U$1") (pin "10B") (pinfunction "EDGE_10B") (pintype "bidirectional"))
    )
    (net (code "48") (name "/D5'") (class "Default")
      (node (ref "IC15") (pin "14") (pinfunction "DO_14") (pintype "bidirectional"))
      (node (ref "IC15") (pin "2") (pinfunction "DI_2") (pintype "bidirectional"))
      (node (ref "IC3") (pin "30") (pinfunction "D5_30") (pintype "bidirectional"))
      (node (ref "R6") (pin "1") (pinfunction "1_1") (pintype "passive"))
    )
    (net (code "49") (name "/D6") (class "Default")
      (node (ref "IC1") (pin "10") (pinfunction "D6_10") (pintype "bidirectional"))
      (node (ref "IC10") (pin "13") (pinfunction "Y6_13") (pintype "tri_state"))
      (node (ref "IC2") (pin "18") (pinfunction "O6_18") (pintype "tri_state"))
      (node (ref "IC22") (pin "15") (pinfunction "I/O3_15") (pintype "bidirectional"))
      (node (ref "IC24") (pin "15") (pinfunction "I/O3_15") (pintype "bidirectional"))
      (node (ref "R23") (pin "1") (pinfunction "1_1") (pintype "passive"))
      (node (ref "R7") (pin "2") (pinfunction "2_2") (pintype "passive"))
      (node (ref "U$1") (pin "9B") (pinfunction "EDGE_9B") (pintype "bidirectional"))
    )
    (net (code "50") (name "/D6'") (class "Default")
      (node (ref "IC14") (pin "14") (pinfunction "DO_14") (pintype "bidirectional"))
      (node (ref "IC14") (pin "2") (pinfunction "DI_2") (pintype "bidirectional"))
      (node (ref "IC3") (pin "31") (pinfunction "D6_31") (pintype "bidirectional"))
      (node (ref "R7") (pin "1") (pinfunction "1_1") (pintype "passive"))
    )
    (net (code "51") (name "/D7") (class "Default")
      (node (ref "D1") (pin "A") (pinfunction "A_A") (pintype "bidirectional"))
      (node (ref "IC1") (pin "13") (pinfunction "D7_13") (pintype "bidirectional"))
      (node (ref "IC2") (pin "19") (pinfunction "O7_19") (pintype "tri_state"))
      (node (ref "IC22") (pin "17") (pinfunction "I/O4_17") (pintype "bidirectional"))
      (node (ref "IC24") (pin "17") (pinfunction "I/O4_17") (pintype "bidirectional"))
      (node (ref "R24") (pin "1") (pinfunction "1_1") (pintype "passive"))
      (node (ref "R8") (pin "2") (pinfunction "2_2") (pintype "passive"))
      (node (ref "U$1") (pin "3B") (pinfunction "EDGE_3B") (pintype "bidirectional"))
    )
    (net (code "52") (name "/D7'") (class "Default")
      (node (ref "IC13") (pin "14") (pinfunction "DO_14") (pintype "bidirectional"))
      (node (ref "IC13") (pin "2") (pinfunction "DI_2") (pintype "bidirectional"))
      (node (ref "IC3") (pin "32") (pinfunction "D7_32") (pintype "bidirectional"))
      (node (ref "R8") (pin "1") (pinfunction "1_1") (pintype "passive"))
    )
    (net (code "53") (name "/MREQ'") (class "Default")
      (node (ref "D10") (pin "C") (pinfunction "K_C") (pintype "bidirectional"))
      (node (ref "IC3") (pin "15") (pinfunction "~{MREQ}_15") (pintype "input"))
      (node (ref "R34") (pin "2") (pinfunction "2_2") (pintype "passive"))
    )
    (net (code "54") (name "/N$33") (class "Default")
      (node (ref "C26") (pin "1") (pinfunction "1_1") (pintype "passive"))
      (node (ref "C27") (pin "1") (pinfunction "1_1") (pintype "passive"))
      (node (ref "IC13") (pin "1") (pinfunction "VBB_1") (pintype "input"))
      (node (ref "IC14") (pin "1") (pinfunction "VBB_1") (pintype "input"))
      (node (ref "IC15") (pin "1") (pinfunction "VBB_1") (pintype "input"))
      (node (ref "IC16") (pin "1") (pinfunction "VBB_1") (pintype "input"))
      (node (ref "IC17") (pin "1") (pinfunction "VBB_1") (pintype "input"))
      (node (ref "IC18") (pin "1") (pinfunction "VBB_1") (pintype "input"))
      (node (ref "IC19") (pin "1") (pinfunction "VBB_1") (pintype "input"))
      (node (ref "IC20") (pin "1") (pinfunction "VBB_1") (pintype "input"))
      (node (ref "J3") (pin "2") (pinfunction "2_2") (pintype "passive"))
    )
    (net (code "55") (name "/RESET") (class "Default")
      (node (ref "D10") (pin "A") (pinfunction "A_A") (pintype "bidirectional"))
      (node (ref "IC28") (pin "12") (pinfunction "O_12") (pintype "output"))
    )
    (net (code "56") (name "/SNDIN") (class "Default")
      (node (ref "C54") (pin "1") (pinfunction "1_1") (pintype "passive"))
      (node (ref "C57") (pin "1") (pinfunction "1_1") (pintype "passive"))
      (node (ref "D13") (pin "A") (pinfunction "A_A") (pintype "bidirectional"))
      (node (ref "D14") (pin "C") (pinfunction "C_C") (pintype "passive"))
      (node (ref "Q7") (pin "2") (pinfunction "B_2") (pintype "passive"))
      (node (ref "R40") (pin "1") (pinfunction "1_1") (pintype "passive"))
      (node (ref "R41") (pin "2") (pinfunction "2_2") (pintype "passive"))
      (node (ref "R42") (pin "2") (pinfunction "2_2") (pintype "passive"))
      (node (ref "TP3") (pin "1") (pinfunction "TP_1") (pintype "input"))
    )
    (net (code "57") (name "/{slash}INT") (class "Default")
      (node (ref "IC1") (pin "16") (pinfunction "~{INT}_16") (pintype "input"))
      (node (ref "R25") (pin "2") (pinfunction "2_2") (pintype "passive"))
      (node (ref "TP10") (pin "1") (pinfunction "TP_1") (pintype "input"))
      (node (ref "U$1") (pin "13B") (pinfunction "EDGE_13B") (pintype "bidirectional"))
    )
    (net (code "58") (name "/~{A}{slash}B") (class "Default")
      (node (ref "IC27") (pin "3") (pinfunction "O_3") (pintype "output"))
      (node (ref "IC6") (pin "1") (pinfunction "~{A}/B_1") (pintype "input"))
      (node (ref "IC7") (pin "1") (pinfunction "~{A}/B_1") (pintype "input"))
      (node (ref "R45") (pin "1") (pinfunction "1_1") (pintype "passive"))
    )
    (net (code "59") (name "/~{CAS0}") (class "Default")
      (node (ref "IC23") (pin "1") (pinfunction "~{OE}_1") (pintype "input"))
      (node (ref "IC23") (pin "16") (pinfunction "~{CAS}_16") (pintype "input"))
      (node (ref "IC24") (pin "1") (pinfunction "~{OE}_1") (pintype "input"))
      (node (ref "IC24") (pin "16") (pinfunction "~{CAS}_16") (pintype "input"))
      (node (ref "IC25") (pin "8") (pinfunction "O_8") (pintype "output"))
    )
    (net (code "60") (name "/~{CAS1}") (class "Default")
      (node (ref "IC21") (pin "1") (pinfunction "~{OE}_1") (pintype "input"))
      (node (ref "IC21") (pin "16") (pinfunction "~{CAS}_16") (pintype "input"))
      (node (ref "IC22") (pin "1") (pinfunction "~{OE}_1") (pintype "input"))
      (node (ref "IC22") (pin "16") (pinfunction "~{CAS}_16") (pintype "input"))
      (node (ref "IC25") (pin "6") (pinfunction "O_6") (pintype "output"))
    )
    (net (code "61") (name "/~{IORQGE}") (class "Default")
      (node (ref "IC3") (pin "2") (pinfunction "~{CS}_2") (pintype "input"))
      (node (ref "Q1") (pin "1") (pinfunction "E_1") (pintype "passive"))
      (node (ref "R27") (pin "2") (pinfunction "2_2") (pintype "passive"))
      (node (ref "U$1") (pin "13A") (pinfunction "EDGE_13A") (pintype "bidirectional"))
    )
    (net (code "62") (name "/~{IORQ}") (class "Default")
      (node (ref "IC1") (pin "20") (pinfunction "~{IORQ}_20") (pintype "output"))
      (node (ref "R27") (pin "1") (pinfunction "1_1") (pintype "passive"))
      (node (ref "U$1") (pin "17B") (pinfunction "EDGE_17B") (pintype "bidirectional"))
    )
    (net (code "63") (name "/~{KBD}") (class "Default")
      (node (ref "D1") (pin "C") (pinfunction "K_C") (pintype "bidirectional"))
      (node (ref "IC10") (pin "1") (pinfunction "G1_1") (pintype "input"))
      (node (ref "IC3") (pin "10") (pinfunction "~{KBD}_10") (pintype "output"))
    )
    (net (code "64") (name "/~{MREQ}") (class "Default")
      (node (ref "IC1") (pin "19") (pinfunction "~{MREQ}_19") (pintype "output"))
      (node (ref "IC2") (pin "22") (pinfunction "~{OE}_22") (pintype "input"))
      (node (ref "IC27") (pin "4") (pinfunction "I0_4") (pintype "input"))
      (node (ref "R34") (pin "1") (pinfunction "1_1") (pintype "passive"))
      (node (ref "U$1") (pin "16B") (pinfunction "EDGE_16B") (pintype "bidirectional"))
    )
    (net (code "65") (name "/~{RAS}") (class "Default")
      (node (ref "IC21") (pin "5") (pinfunction "~{RAS}_5") (pintype "input"))
      (node (ref "IC22") (pin "5") (pinfunction "~{RAS}_5") (pintype "input"))
      (node (ref "IC23") (pin "5") (pinfunction "~{RAS}_5") (pintype "input"))
      (node (ref "IC24") (pin "5") (pinfunction "~{RAS}_5") (pintype "input"))
      (node (ref "IC27") (pin "6") (pinfunction "O_6") (pintype "output"))
      (node (ref "IC27") (pin "9") (pinfunction "I0_9") (pintype "input"))
      (node (ref "R28") (pin "1") (pinfunction "1_1") (pintype "passive"))
    )
    (net (code "66") (name "/~{RD}") (class "Default")
      (node (ref "IC1") (pin "21") (pinfunction "~{RD}_21") (pintype "output"))
      (node (ref "IC2") (pin "27") (pinfunction "~{PGM}_27") (pintype "input"))
      (node (ref "IC25") (pin "2") (pinfunction "I1_2") (pintype "input"))
      (node (ref "IC3") (pin "17") (pinfunction "~{RD}_17") (pintype "input"))
      (node (ref "U$1") (pin "18B") (pinfunction "EDGE_18B") (pintype "bidirectional"))
    )
    (net (code "67") (name "/~{RESET}") (class "Default")
      (node (ref "C17") (pin "1") (pinfunction "1_1") (pintype "passive"))
      (node (ref "IC1") (pin "26") (pinfunction "~{RESET}_26") (pintype "input"))
      (node (ref "IC28") (pin "13") (pinfunction "I_13") (pintype "input"))
      (node (ref "R29") (pin "1") (pinfunction "1_1") (pintype "passive"))
      (node (ref "U$1") (pin "20A") (pinfunction "EDGE_20A") (pintype "bidirectional"))
    )
    (net (code "68") (name "/~{RFSH}") (class "Default")
      (node (ref "IC1") (pin "28") (pinfunction "~{RFSH}_28") (pintype "output"))
      (node (ref "IC26") (pin "13") (pinfunction "I1_13") (pintype "input"))
      (node (ref "IC26") (pin "2") (pinfunction "I1_2") (pintype "input"))
      (node (ref "IC5") (pin "11") (pinfunction "CLK_11") (pintype "input"))
      (node (ref "U$1") (pin "25B") (pinfunction "EDGE_25B") (pintype "bidirectional"))
    )
    (net (code "69") (name "/~{ROMCS}") (class "Default")
      (node (ref "IC2") (pin "20") (pinfunction "~{CE}_20") (pintype "input"))
      (node (ref "R26") (pin "2") (pinfunction "2_2") (pintype "passive"))
      (node (ref "TP9") (pin "1") (pinfunction "TP_1") (pintype "input"))
      (node (ref "U$1") (pin "25A") (pinfunction "EDGE_25A") (pintype "bidirectional"))
    )
    (net (code "70") (name "/~{ULAINT}") (class "Default")
      (node (ref "IC3") (pin "34") (pinfunction "~{INT}_34") (pintype "output"))
      (node (ref "R25") (pin "1") (pinfunction "1_1") (pintype "passive"))
    )
    (net (code "71") (name "/~{VCAS}") (class "Default")
      (node (ref "IC13") (pin "15") (pinfunction "~{CAS}_15") (pintype "input"))
      (node (ref "IC14") (pin "15") (pinfunction "~{CAS}_15") (pintype "input"))
      (node (ref "IC15") (pin "15") (pinfunction "~{CAS}_15") (pintype "input"))
      (node (ref "IC16") (pin "15") (pinfunction "~{CAS}_15") (pintype "input"))
      (node (ref "IC17") (pin "15") (pinfunction "~{CAS}_15") (pintype "input"))
      (node (ref "IC18") (pin "15") (pinfunction "~{CAS}_15") (pintype "input"))
      (node (ref "IC19") (pin "15") (pinfunction "~{CAS}_15") (pintype "input"))
      (node (ref "IC20") (pin "15") (pinfunction "~{CAS}_15") (pintype "input"))
      (node (ref "IC3") (pin "12") (pinfunction "~{VCAS}_12") (pintype "output"))
      (node (ref "TP5") (pin "1") (pinfunction "TP_1") (pintype "input"))
    )
    (net (code "72") (name "/~{VRAS}") (class "Default")
      (node (ref "IC13") (pin "4") (pinfunction "~{RAS}_4") (pintype "input"))
      (node (ref "IC14") (pin "4") (pinfunction "~{RAS}_4") (pintype "input"))
      (node (ref "IC15") (pin "4") (pinfunction "~{RAS}_4") (pintype "input"))
      (node (ref "IC16") (pin "4") (pinfunction "~{RAS}_4") (pintype "input"))
      (node (ref "IC17") (pin "4") (pinfunction "~{RAS}_4") (pintype "input"))
      (node (ref "IC18") (pin "4") (pinfunction "~{RAS}_4") (pintype "input"))
      (node (ref "IC19") (pin "4") (pinfunction "~{RAS}_4") (pintype "input"))
      (node (ref "IC20") (pin "4") (pinfunction "~{RAS}_4") (pintype "input"))
      (node (ref "IC3") (pin "13") (pinfunction "~{VRAS}_13") (pintype "output"))
      (node (ref "R16") (pin "2") (pinfunction "2_2") (pintype "passive"))
      (node (ref "TP4") (pin "1") (pinfunction "TP_1") (pintype "input"))
    )
    (net (code "73") (name "/~{VWR}") (class "Default")
      (node (ref "IC13") (pin "3") (pinfunction "~{WE}_3") (pintype "input"))
      (node (ref "IC14") (pin "3") (pinfunction "~{WE}_3") (pintype "input"))
      (node (ref "IC15") (pin "3") (pinfunction "~{WE}_3") (pintype "input"))
      (node (ref "IC16") (pin "3") (pinfunction "~{WE}_3") (pintype "input"))
      (node (ref "IC17") (pin "3") (pinfunction "~{WE}_3") (pintype "input"))
      (node (ref "IC18") (pin "3") (pinfunction "~{WE}_3") (pintype "input"))
      (node (ref "IC19") (pin "3") (pinfunction "~{WE}_3") (pintype "input"))
      (node (ref "IC20") (pin "3") (pinfunction "~{WE}_3") (pintype "input"))
      (node (ref "IC3") (pin "14") (pinfunction "~{VWR}_14") (pintype "output"))
      (node (ref "TP6") (pin "1") (pinfunction "TP_1") (pintype "input"))
    )
    (net (code "74") (name "/~{WR}") (class "Default")
      (node (ref "IC1") (pin "22") (pinfunction "~{WR}_22") (pintype "output"))
      (node (ref "IC21") (pin "4") (pinfunction "~{WE}_4") (pintype "input"))
      (node (ref "IC22") (pin "4") (pinfunction "~{WE}_4") (pintype "input"))
      (node (ref "IC23") (pin "4") (pinfunction "~{WE}_4") (pintype "input"))
      (node (ref "IC24") (pin "4") (pinfunction "~{WE}_4") (pintype "input"))
      (node (ref "IC25") (pin "1") (pinfunction "I0_1") (pintype "input"))
      (node (ref "IC3") (pin "16") (pinfunction "~{WR}_16") (pintype "input"))
      (node (ref "U$1") (pin "19B") (pinfunction "EDGE_19B") (pintype "bidirectional"))
    )
    (net (code "75") (name "AUDIO") (class "Default")
      (node (ref "C36") (pin "2") (pinfunction "2_2") (pintype "passive"))
      (node (ref "C54") (pin "2") (pinfunction "2_2") (pintype "passive"))
      (node (ref "C55") (pin "1") (pinfunction "1_1") (pintype "passive"))
      (node (ref "D25_") (pin "A") (pinfunction "A_A") (pintype "bidirectional"))
      (node (ref "J4") (pin "1") (pinfunction "1_1") (pintype "passive"))
      (node (ref "R53") (pin "1") (pinfunction "1_1") (pintype "passive"))
      (node (ref "R54") (pin "2") (pinfunction "2_2") (pintype "passive"))
    )
    (net (code "76") (name "GND") (class "Default")
      (node (ref "7805") (pin "GND") (pinfunction "GND_GND") (pintype "input"))
      (node (ref "C1") (pin "-") (pinfunction "-_-") (pintype "passive"))
      (node (ref "C10") (pin "2") (pinfunction "2_2") (pintype "passive"))
      (node (ref "C11") (pin "2") (pinfunction "2_2") (pintype "passive"))
      (node (ref "C12") (pin "1") (pinfunction "1_1") (pintype "passive"))
      (node (ref "C13") (pin "1") (pinfunction "1_1") (pintype "passive"))
      (node (ref "C14") (pin "1") (pinfunction "1_1") (pintype "passive"))
      (node (ref "C15") (pin "2") (pinfunction "2_2") (pintype "passive"))
      (node (ref "C16") (pin "2") (pinfunction "2_2") (pintype "passive"))
      (node (ref "C17") (pin "2") (pinfunction "2_2") (pintype "passive"))
      (node (ref "C18") (pin "2") (pinfunction "2_2") (pintype "passive"))
      (node (ref "C19") (pin "2") (pinfunction "2_2") (pintype "passive"))
      (node (ref "C2") (pin "-") (pinfunction "-_-") (pintype "passive"))
      (node (ref "C20") (pin "2") (pinfunction "2_2") (pintype "passive"))
      (node (ref "C21") (pin "2") (pinfunction "2_2") (pintype "passive"))
      (node (ref "C22") (pin "1") (pinfunction "1_1") (pintype "passive"))
      (node (ref "C23") (pin "2") (pinfunction "2_2") (pintype "passive"))
      (node (ref "C24") (pin "1") (pinfunction "1_1") (pintype "passive"))
      (node (ref "C25") (pin "2") (pinfunction "2_2") (pintype "passive"))
      (node (ref "C26") (pin "2") (pinfunction "2_2") (pintype "passive"))
      (node (ref "C27") (pin "2") (pinfunction "2_2") (pintype "passive"))
      (node (ref "C28") (pin "2") (pinfunction "2_2") (pintype "passive"))
      (node (ref "C29") (pin "1") (pinfunction "1_1") (pintype "passive"))
      (node (ref "C3") (pin "1") (pinfunction "1_1") (pintype "passive"))
      (node (ref "C30") (pin "2") (pinfunction "2_2") (pintype "passive"))
      (node (ref "C31") (pin "1") (pinfunction "1_1") (pintype "passive"))
      (node (ref "C32") (pin "1") (pinfunction "1_1") (pintype "passive"))
      (node (ref "C33") (pin "1") (pinfunction "1_1") (pintype "passive"))
      (node (ref "C40") (pin "1") (pinfunction "1_1") (pintype "passive"))
      (node (ref "C43") (pin "1") (pinfunction "1_1") (pintype "passive"))
      (node (ref "C44") (pin "2") (pinfunction "2_2") (pintype "passive"))
      (node (ref "C45") (pin "2") (pinfunction "2_2") (pintype "passive"))
      (node (ref "C46") (pin "2") (pinfunction "2_2") (pintype "passive"))
      (node (ref "C49") (pin "+") (pinfunction "+_+") (pintype "passive"))
      (node (ref "C50") (pin "2") (pinfunction "2_2") (pintype "passive"))
      (node (ref "C52") (pin "-") (pinfunction "-_-") (pintype "passive"))
      (node (ref "C53") (pin "-") (pinfunction "-_-") (pintype "passive"))
      (node (ref "C56") (pin "1") (pinfunction "1_1") (pintype "passive"))
      (node (ref "C57") (pin "2") (pinfunction "2_2") (pintype "passive"))
      (node (ref "C6") (pin "1") (pinfunction "1_1") (pintype "passive"))
      (node (ref "C8") (pin "1") (pinfunction "1_1") (pintype "passive"))
      (node (ref "D14") (pin "A") (pinfunction "A_A") (pintype "passive"))
      (node (ref "D16") (pin "A") (pinfunction "A_A") (pintype "bidirectional"))
      (node (ref "D18") (pin "A") (pinfunction "A_A") (pintype "bidirectional"))
      (node (ref "D20") (pin "C") (pinfunction "K_C") (pintype "bidirectional"))
      (node (ref "D21") (pin "C") (pinfunction "K_C") (pintype "bidirectional"))
      (node (ref "D24") (pin "A") (pinfunction "A_A") (pintype "bidirectional"))
      (node (ref "EAR") (pin "RING") (pinfunction "SHIELD_RING") (pintype "passive"))
      (node (ref "IC1") (pin "29") (pinfunction "GND_29") (pintype "power_in"))
      (node (ref "IC10") (pin "15") (pinfunction "G2_15") (pintype "input"))
      (node (ref "IC10") (pin "8") (pinfunction "GND_8") (pintype "power_in"))
      (node (ref "IC11") (pin "10") (pinfunction "GND_10") (pintype "power_in"))
      (node (ref "IC12") (pin "5") (pinfunction "GND_5") (pintype "power_in"))
      (node (ref "IC13") (pin "16") (pinfunction "VSS_16") (pintype "power_in"))
      (node (ref "IC14") (pin "16") (pinfunction "VSS_16") (pintype "power_in"))
      (node (ref "IC15") (pin "16") (pinfunction "VSS_16") (pintype "power_in"))
      (node (ref "IC16") (pin "16") (pinfunction "VSS_16") (pintype "power_in"))
      (node (ref "IC17") (pin "16") (pinfunction "VSS_16") (pintype "power_in"))
      (node (ref "IC18") (pin "16") (pinfunction "VSS_16") (pintype "power_in"))
      (node (ref "IC19") (pin "16") (pinfunction "VSS_16") (pintype "power_in"))
      (node (ref "IC2") (pin "14") (pinfunction "GND_14") (pintype "power_in"))
      (node (ref "IC20") (pin "16") (pinfunction "VSS_16") (pintype "power_in"))
      (node (ref "IC21") (pin "18") (pinfunction "GND_18") (pintype "power_in"))
      (node (ref "IC22") (pin "18") (pinfunction "GND_18") (pintype "power_in"))
      (node (ref "IC23") (pin "18") (pinfunction "GND_18") (pintype "power_in"))
      (node (ref "IC24") (pin "18") (pinfunction "GND_18") (pintype "power_in"))
      (node (ref "IC25") (pin "7") (pinfunction "GND_7") (pintype "power_in"))
      (node (ref "IC26") (pin "7") (pinfunction "GND_7") (pintype "power_in"))
      (node (ref "IC27") (pin "5") (pinfunction "I1_5") (pintype "input"))
      (node (ref "IC27") (pin "7") (pinfunction "GND_7") (pintype "power_in"))
      (node (ref "IC28") (pin "7") (pinfunction "GND_7") (pintype "power_in"))
      (node (ref "IC3") (pin "20") (pinfunction "GND_20") (pintype "power_in"))
      (node (ref "IC4") (pin "7") (pinfunction "GND_7") (pintype "power_in"))
      (node (ref "IC5") (pin "7") (pinfunction "GND_7") (pintype "power_in"))
      (node (ref "IC6") (pin "15") (pinfunction "G_15") (pintype "input"))
      (node (ref "IC6") (pin "8") (pinfunction "GND_8") (pintype "power_in"))
      (node (ref "IC7") (pin "15") (pinfunction "G_15") (pintype "input"))
      (node (ref "IC7") (pin "8") (pinfunction "GND_8") (pintype "power_in"))
      (node (ref "IC8") (pin "15") (pinfunction "G_15") (pintype "input"))
      (node (ref "IC8") (pin "8") (pinfunction "GND_8") (pintype "power_in"))
      (node (ref "IC9") (pin "15") (pinfunction "G_15") (pintype "input"))
      (node (ref "IC9") (pin "8") (pinfunction "GND_8") (pintype "power_in"))
      (node (ref "MIC") (pin "RING") (pinfunction "SHIELD_RING") (pintype "passive"))
      (node (ref "Q2") (pin "1") (pinfunction "E_1") (pintype "passive"))
      (node (ref "Q4") (pin "1") (pinfunction "E_1") (pintype "passive"))
      (node (ref "Q6") (pin "C") (pinfunction "C_C") (pintype "passive"))
      (node (ref "Q7") (pin "1") (pinfunction "E_1") (pintype "passive"))
      (node (ref "R33") (pin "2") (pinfunction "2_2") (pintype "passive"))
      (node (ref "R41") (pin "1") (pinfunction "1_1") (pintype "passive"))
      (node (ref "R47") (pin "1") (pinfunction "1_1") (pintype "passive"))
      (node (ref "R50") (pin "1") (pinfunction "1_1") (pintype "passive"))
      (node (ref "R53") (pin "2") (pinfunction "2_2") (pintype "passive"))
      (node (ref "R55") (pin "2") (pinfunction "2_2") (pintype "passive"))
      (node (ref "R65") (pin "2") (pinfunction "2_2") (pintype "passive"))
      (node (ref "R69") (pin "1") (pinfunction "1_1") (pintype "passive"))
      (node (ref "R70") (pin "1") (pinfunction "1_1") (pintype "passive"))
      (node (ref "R73_") (pin "2") (pinfunction "2_2") (pintype "passive"))
      (node (ref "R76") (pin "2") (pinfunction "2_2") (pintype "passive"))
      (node (ref "U$1") (pin "14A") (pinfunction "EDGE_14A") (pintype "bidirectional"))
      (node (ref "U$1") (pin "6A") (pinfunction "EDGE_6A") (pintype "bidirectional"))
      (node (ref "U$1") (pin "7A") (pinfunction "EDGE_7A") (pintype "bidirectional"))
      (node (ref "X1") (pin "SHELL") (pinfunction "2_SHELL") (pintype "passive"))
      (node (ref "X1") (pin "SHELL@1") (pinfunction "2_SHELL@1") (pintype "passive"))
      (node (ref "X1") (pin "SHELL@2") (pinfunction "2_SHELL@2") (pintype "passive"))
      (node (ref "X2") (pin "RING") (pinfunction "SHIELD_RING") (pintype "passive"))
    )
    (net (code "77") (name "Net-(C5-Pad1)") (class "Default")
      (node (ref "C5") (pin "1") (pinfunction "1_1") (pintype "passive"))
      (node (ref "R42") (pin "1") (pinfunction "1_1") (pintype "passive"))
    )
    (net (code "78") (name "Net-(C5-Pad2)") (class "Default")
      (node (ref "C5") (pin "2") (pinfunction "2_2") (pintype "passive"))
      (node (ref "EAR") (pin "NC") (pinfunction "NC_NC") (pintype "passive"))
      (node (ref "EAR") (pin "TIP") (pinfunction "TIP_TIP") (pintype "passive"))
      (node (ref "R70") (pin "2") (pinfunction "2_2") (pintype "passive"))
    )
    (net (code "79") (name "Net-(C7-Pad1)") (class "Default")
      (node (ref "C7") (pin "1") (pinfunction "1_1") (pintype "passive"))
      (node (ref "XTAL") (pin "2") (pinfunction "2_2") (pintype "passive"))
    )
    (net (code "80") (name "Net-(C8-Pad2)") (class "Default")
      (node (ref "C8") (pin "2") (pinfunction "2_2") (pintype "passive"))
      (node (ref "Q3") (pin "B") (pinfunction "B_B") (pintype "passive"))
      (node (ref "R44") (pin "2") (pinfunction "2_2") (pintype "passive"))
      (node (ref "XTAL") (pin "1") (pinfunction "1_1") (pintype "passive"))
    )
    (net (code "81") (name "Net-(C37-Pad1)") (class "Default")
      (node (ref "C37") (pin "1") (pinfunction "1_1") (pintype "passive"))
      (node (ref "C38") (pin "2") (pinfunction "2_2") (pintype "passive"))
      (node (ref "R55") (pin "1") (pinfunction "1_1") (pintype "passive"))
    )
    (net (code "82") (name "Net-(C38-Pad1)") (class "Default")
      (node (ref "C38") (pin "1") (pinfunction "1_1") (pintype "passive"))
      (node (ref "C39") (pin "2") (pinfunction "2_2") (pintype "passive"))
      (node (ref "R56") (pin "1") (pinfunction "1_1") (pintype "passive"))
    )
    (net (code "83") (name "Net-(C39-Pad1)") (class "Default")
      (node (ref "C39") (pin "1") (pinfunction "1_1") (pintype "passive"))
      (node (ref "L2") (pin "2") (pinfunction "2_2") (pintype "passive"))
    )
    (net (code "84") (name "Net-(C49-Pad-)") (class "Default")
      (node (ref "C49") (pin "-") (pinfunction "-_-") (pintype "passive"))
      (node (ref "D19") (pin "A") (pinfunction "A_A") (pintype "bidirectional"))
      (node (ref "R67") (pin "2") (pinfunction "2_2") (pintype "passive"))
    )
    (net (code "85") (name "Net-(C56-Pad2)") (class "Default")
      (node (ref "C56") (pin "2") (pinfunction "2_2") (pintype "passive"))
      (node (ref "L2") (pin "1") (pinfunction "1_1") (pintype "passive"))
      (node (ref "R71") (pin "1") (pinfunction "1_1") (pintype "passive"))
      (node (ref "R72") (pin "2") (pinfunction "2_2") (pintype "passive"))
    )
    (net (code "86") (name "Net-(C58-Pad+)") (class "Default")
      (node (ref "C58") (pin "+") (pinfunction "+_+") (pintype "passive"))
      (node (ref "Q8") (pin "E") (pinfunction "E_E") (pintype "passive"))
      (node (ref "R76") (pin "1") (pinfunction "1_1") (pintype "passive"))
    )
    (net (code "87") (name "Net-(D2-PadA)") (class "Default")
      (node (ref "D2") (pin "A") (pinfunction "A_A") (pintype "bidirectional"))
      (node (ref "KB2") (pin "3") (pinfunction "3_3") (pintype "passive"))
    )
    (net (code "88") (name "Net-(D3-PadA)") (class "Default")
      (node (ref "D3") (pin "A") (pinfunction "A_A") (pintype "bidirectional"))
      (node (ref "KB2") (pin "6") (pinfunction "6_6") (pintype "passive"))
    )
    (net (code "89") (name "Net-(D4-PadA)") (class "Default")
      (node (ref "D4") (pin "A") (pinfunction "A_A") (pintype "bidirectional"))
      (node (ref "KB2") (pin "7") (pinfunction "7_7") (pintype "passive"))
    )
    (net (code "90") (name "Net-(D7-PadA)") (class "Default")
      (node (ref "D7") (pin "A") (pinfunction "A_A") (pintype "bidirectional"))
      (node (ref "KB2") (pin "4") (pinfunction "4_4") (pintype "passive"))
    )
    (net (code "91") (name "Net-(D8-PadA)") (class "Default")
      (node (ref "D8") (pin "A") (pinfunction "A_A") (pintype "bidirectional"))
      (node (ref "KB2") (pin "2") (pinfunction "2_2") (pintype "passive"))
    )
    (net (code "92") (name "Net-(D9-PadA)") (class "Default")
      (node (ref "D9") (pin "A") (pinfunction "A_A") (pintype "bidirectional"))
      (node (ref "KB2") (pin "1") (pinfunction "1_1") (pintype "passive"))
    )
    (net (code "93") (name "Net-(D11-K)") (class "Default")
      (node (ref "D11") (pin "C") (pinfunction "K_C") (pintype "bidirectional"))
      (node (ref "D12") (pin "C") (pinfunction "K_C") (pintype "bidirectional"))
      (node (ref "IC27") (pin "11") (pinfunction "O_11") (pintype "output"))
      (node (ref "R26") (pin "1") (pinfunction "1_1") (pintype "passive"))
      (node (ref "R33") (pin "1") (pinfunction "1_1") (pintype "passive"))
    )
    (net (code "94") (name "Net-(D16-K)") (class "Default")
      (node (ref "C36") (pin "1") (pinfunction "1_1") (pintype "passive"))
      (node (ref "D15") (pin "A") (pinfunction "A_A") (pintype "bidirectional"))
      (node (ref "D16") (pin "C") (pinfunction "K_C") (pintype "bidirectional"))
      (node (ref "IC3") (pin "24") (pinfunction "BEEP_24") (pintype "output"))
      (node (ref "TP7") (pin "1") (pinfunction "TP_1") (pintype "input"))
    )
    (net (code "95") (name "Net-(D19-K)") (class "Default")
      (node (ref "C48") (pin "2") (pinfunction "2_2") (pintype "passive"))
      (node (ref "D19") (pin "C") (pinfunction "K_C") (pintype "bidirectional"))
      (node (ref "D20") (pin "A") (pinfunction "A_A") (pintype "bidirectional"))
    )
    (net (code "96") (name "Net-(D22-K)") (class "Default")
      (node (ref "C51") (pin "2") (pinfunction "2_2") (pintype "passive"))
      (node (ref "D22") (pin "C") (pinfunction "K_C") (pintype "bidirectional"))
      (node (ref "D23") (pin "A") (pinfunction "A_A") (pintype "bidirectional"))
    )
    (net (code "97") (name "Net-(D23-K)") (class "Default")
      (node (ref "C52") (pin "+") (pinfunction "+_+") (pintype "passive"))
      (node (ref "D23") (pin "C") (pinfunction "K_C") (pintype "bidirectional"))
      (node (ref "R68") (pin "2") (pinfunction "2_2") (pintype "passive"))
    )
    (net (code "98") (name "Net-(D27-K)") (class "Default")
      (node (ref "D25") (pin "C") (pinfunction "C_C") (pintype "passive"))
      (node (ref "D26") (pin "C") (pinfunction "C_C") (pintype "passive"))
      (node (ref "D27") (pin "C") (pinfunction "K_C") (pintype "bidirectional"))
      (node (ref "IC3") (pin "18") (pinfunction "BRIGHT_18") (pintype "output"))
    )
    (net (code "99") (name "Net-(IC1-CLK)") (class "Default")
      (node (ref "IC1") (pin "6") (pinfunction "CLK_6") (pintype "input"))
      (node (ref "Q2") (pin "3") (pinfunction "C_3") (pintype "passive"))
      (node (ref "R48") (pin "1") (pinfunction "1_1") (pintype "passive"))
      (node (ref "TP1") (pin "1") (pinfunction "TP_1") (pintype "input"))
    )
    (net (code "100") (name "Net-(IC1-~{BUSAK})") (class "Default")
      (node (ref "IC1") (pin "23") (pinfunction "~{BUSAK}_23") (pintype "output"))
      (node (ref "U$1") (pin "26A") (pinfunction "EDGE_26A") (pintype "bidirectional"))
    )
    (net (code "101") (name "Net-(IC1-~{BUSRQ})") (class "Default")
      (node (ref "IC1") (pin "25") (pinfunction "~{BUSRQ}_25") (pintype "input"))
      (node (ref "R30") (pin "2") (pinfunction "2_2") (pintype "passive"))
      (node (ref "U$1") (pin "19A") (pinfunction "EDGE_19A") (pintype "bidirectional"))
    )
    (net (code "102") (name "Net-(IC1-~{HALT})") (class "Default")
      (node (ref "IC1") (pin "18") (pinfunction "~{HALT}_18") (pintype "output"))
      (node (ref "U$1") (pin "15B") (pinfunction "EDGE_15B") (pintype "bidirectional"))
    )
    (net (code "103") (name "Net-(IC1-~{M1})") (class "Default")
      (node (ref "IC1") (pin "27") (pinfunction "~{M1}_27") (pintype "output"))
      (node (ref "U$1") (pin "24B") (pinfunction "EDGE_24B") (pintype "bidirectional"))
    )
    (net (code "104") (name "Net-(IC1-~{NMI})") (class "Default")
      (node (ref "IC1") (pin "17") (pinfunction "~{NMI}_17") (pintype "input"))
      (node (ref "R31") (pin "2") (pinfunction "2_2") (pintype "passive"))
      (node (ref "U$1") (pin "14B") (pinfunction "EDGE_14B") (pintype "bidirectional"))
    )
    (net (code "105") (name "Net-(IC1-~{WAIT})") (class "Default")
      (node (ref "IC1") (pin "24") (pinfunction "~{WAIT}_24") (pintype "input"))
      (node (ref "R32") (pin "2") (pinfunction "2_2") (pintype "passive"))
      (node (ref "U$1") (pin "21B") (pinfunction "EDGE_21B") (pintype "bidirectional"))
    )
    (net (code "106") (name "Net-(IC3-MIC)") (class "Default")
      (node (ref "IC3") (pin "23") (pinfunction "MIC_23") (pintype "output"))
      (node (ref "R46") (pin "2") (pinfunction "2_2") (pintype "passive"))
    )
    (net (code "107") (name "Net-(IC4B-D)") (class "Default")
      (node (ref "IC4") (pin "12") (pinfunction "D_12") (pintype "input"))
      (node (ref "IC4") (pin "8") (pinfunction "~{Q}_8") (pintype "output"))
    )
    (net (code "108") (name "Net-(IC5A-CLK)") (class "Default")
      (node (ref "IC5") (pin "3") (pinfunction "CLK_3") (pintype "input"))
      (node (ref "IC5") (pin "9") (pinfunction "Q_9") (pintype "output"))
    )
    (net (code "109") (name "Net-(IC5A-D)") (class "Default")
      (node (ref "IC5") (pin "2") (pinfunction "D_2") (pintype "input"))
      (node (ref "IC5") (pin "6") (pinfunction "~{Q}_6") (pintype "output"))
    )
    (net (code "110") (name "Net-(IC8A-1Y)") (class "Default")
      (node (ref "IC8") (pin "4") (pinfunction "1Y_4") (pintype "output"))
      (node (ref "R15") (pin "2") (pinfunction "2_2") (pintype "passive"))
    )
    (net (code "111") (name "Net-(IC8A-2Y)") (class "Default")
      (node (ref "IC8") (pin "7") (pinfunction "2Y_7") (pintype "output"))
      (node (ref "R14") (pin "2") (pinfunction "2_2") (pintype "passive"))
    )
    (net (code "112") (name "Net-(IC8A-3Y)") (class "Default")
      (node (ref "IC8") (pin "9") (pinfunction "3Y_9") (pintype "output"))
      (node (ref "R12") (pin "2") (pinfunction "2_2") (pintype "passive"))
    )
    (net (code "113") (name "Net-(IC8A-4Y)") (class "Default")
      (node (ref "IC8") (pin "12") (pinfunction "4Y_12") (pintype "output"))
      (node (ref "R13") (pin "2") (pinfunction "2_2") (pintype "passive"))
    )
    (net (code "114") (name "Net-(IC8A-~{A}{slash}B)") (class "Default")
      (node (ref "IC8") (pin "1") (pinfunction "~{A}/B_1") (pintype "input"))
      (node (ref "IC9") (pin "1") (pinfunction "~{A}/B_1") (pintype "input"))
      (node (ref "R16") (pin "1") (pinfunction "1_1") (pintype "passive"))
    )
    (net (code "115") (name "Net-(IC9A-2Y)") (class "Default")
      (node (ref "IC9") (pin "7") (pinfunction "2Y_7") (pintype "output"))
      (node (ref "R11") (pin "2") (pinfunction "2_2") (pintype "passive"))
    )
    (net (code "116") (name "Net-(IC9A-3Y)") (class "Default")
      (node (ref "IC9") (pin "9") (pinfunction "3Y_9") (pintype "output"))
      (node (ref "R9") (pin "2") (pinfunction "2_2") (pintype "passive"))
    )
    (net (code "117") (name "Net-(IC9A-4Y)") (class "Default")
      (node (ref "IC9") (pin "12") (pinfunction "4Y_12") (pintype "output"))
      (node (ref "R10") (pin "2") (pinfunction "2_2") (pintype "passive"))
    )
    (net (code "118") (name "Net-(IC10A-A1)") (class "Default")
      (node (ref "IC10") (pin "2") (pinfunction "A1_2") (pintype "input"))
      (node (ref "KB1") (pin "5") (pinfunction "5_5") (pintype "passive"))
      (node (ref "P") (pin "6") (pinfunction "M_6") (pintype "passive"))
      (node (ref "R39") (pin "2") (pinfunction "2_2") (pintype "passive"))
    )
    (net (code "119") (name "Net-(IC10A-A2)") (class "Default")
      (node (ref "IC10") (pin "4") (pinfunction "A2_4") (pintype "input"))
      (node (ref "KB1") (pin "4") (pinfunction "4_4") (pintype "passive"))
      (node (ref "P") (pin "1") (pinfunction "M_1") (pintype "passive"))
      (node (ref "R38") (pin "2") (pinfunction "2_2") (pintype "passive"))
    )
    (net (code "120") (name "Net-(IC10A-A3)") (class "Default")
      (node (ref "IC10") (pin "6") (pinfunction "A3_6") (pintype "input"))
      (node (ref "KB1") (pin "3") (pinfunction "3_3") (pintype "passive"))
      (node (ref "P") (pin "2") (pinfunction "M_2") (pintype "passive"))
      (node (ref "R35") (pin "2") (pinfunction "2_2") (pintype "passive"))
    )
    (net (code "121") (name "Net-(IC10A-A4)") (class "Default")
      (node (ref "IC10") (pin "10") (pinfunction "A4_10") (pintype "input"))
      (node (ref "KB1") (pin "2") (pinfunction "2_2") (pintype "passive"))
      (node (ref "P") (pin "4") (pinfunction "M_4") (pintype "passive"))
      (node (ref "R36") (pin "2") (pinfunction "2_2") (pintype "passive"))
    )
    (net (code "122") (name "Net-(IC10A-A5)") (class "Default")
      (node (ref "IC10") (pin "12") (pinfunction "A5_12") (pintype "input"))
      (node (ref "KB1") (pin "1") (pinfunction "1_1") (pintype "passive"))
      (node (ref "P") (pin "3") (pinfunction "M_3") (pintype "passive"))
      (node (ref "R37") (pin "2") (pinfunction "2_2") (pintype "passive"))
    )
    (net (code "123") (name "Net-(IC10A-A6)") (class "Default")
      (node (ref "IC10") (pin "14") (pinfunction "A6_14") (pintype "input"))
      (node (ref "Q7") (pin "3") (pinfunction "C_3") (pintype "passive"))
      (node (ref "R74_") (pin "1") (pinfunction "1_1") (pintype "passive"))
    )
    (net (code "124") (name "Net-(IC11-B-Y)") (class "Default")
      (node (ref "C45") (pin "1") (pinfunction "1_1") (pintype "passive"))
      (node (ref "IC11") (pin "4") (pinfunction "B-Y_4") (pintype "output"))
      (node (ref "IC12") (pin "4") (pinfunction "B-Y_4") (pintype "input"))
    )
    (net (code "125") (name "Net-(IC11-B1)") (class "Default")
      (node (ref "IC11") (pin "17") (pinfunction "B3_17") (pintype "input"))
      (node (ref "IC11") (pin "19") (pinfunction "B1_19") (pintype "input"))
      (node (ref "IC3") (pin "22") (pinfunction "BLUE_22") (pintype "output"))
      (node (ref "R75") (pin "2") (pinfunction "2_2") (pintype "passive"))
    )
    (net (code "126") (name "Net-(IC11-B2)") (class "Default")
      (node (ref "D27") (pin "A") (pinfunction "A_A") (pintype "bidirectional"))
      (node (ref "IC11") (pin "18") (pinfunction "B2_18") (pintype "input"))
      (node (ref "R75") (pin "1") (pinfunction "1_1") (pintype "passive"))
    )
    (net (code "127") (name "Net-(IC11-BLANK)") (class "Default")
      (node (ref "IC11") (pin "8") (pinfunction "SYNC_8") (pintype "input"))
      (node (ref "IC11") (pin "9") (pinfunction "BLANK_9") (pintype "input"))
      (node (ref "IC3") (pin "33") (pinfunction "SYNC_33") (pintype "output"))
      (node (ref "TP8") (pin "1") (pinfunction "TP_1") (pintype "input"))
    )
    (net (code "128") (name "Net-(IC11-CREF)") (class "Default")
      (node (ref "C46") (pin "1") (pinfunction "1_1") (pintype "passive"))
      (node (ref "IC11") (pin "7") (pinfunction "CREF_7") (pintype "input"))
      (node (ref "IC12") (pin "12") (pinfunction "Y_12") (pintype "input"))
    )
    (net (code "129") (name "Net-(IC11-G1)") (class "Default")
      (node (ref "IC11") (pin "14") (pinfunction "G3_14") (pintype "input"))
      (node (ref "IC11") (pin "16") (pinfunction "G1_16") (pintype "input"))
      (node (ref "IC3") (pin "19") (pinfunction "GREEN_19") (pintype "output"))
      (node (ref "R73") (pin "2") (pinfunction "2_2") (pintype "passive"))
    )
    (net (code "130") (name "Net-(IC11-G2)") (class "Default")
      (node (ref "D25") (pin "A") (pinfunction "A_A") (pintype "passive"))
      (node (ref "IC11") (pin "15") (pinfunction "G2_15") (pintype "input"))
      (node (ref "R73") (pin "1") (pinfunction "1_1") (pintype "passive"))
    )
    (net (code "131") (name "Net-(IC11-GATE)") (class "Default")
      (node (ref "IC11") (pin "1") (pinfunction "GATE_1") (pintype "input"))
      (node (ref "IC28") (pin "6") (pinfunction "O_6") (pintype "output"))
    )
    (net (code "132") (name "Net-(IC11-H{slash}2)") (class "Default")
      (node (ref "IC11") (pin "2") (pinfunction "H/2_2") (pintype "input"))
      (node (ref "IC4") (pin "9") (pinfunction "Q_9") (pintype "output"))
    )
    (net (code "133") (name "Net-(IC11-R-Y)") (class "Default")
      (node (ref "C44") (pin "1") (pinfunction "1_1") (pintype "passive"))
      (node (ref "IC11") (pin "3") (pinfunction "R-Y_3") (pintype "output"))
      (node (ref "IC12") (pin "2") (pinfunction "R-Y_2") (pintype "input"))
    )
    (net (code "134") (name "Net-(IC11-R1)") (class "Default")
      (node (ref "IC11") (pin "11") (pinfunction "R3_11") (pintype "input"))
      (node (ref "IC11") (pin "13") (pinfunction "R1_13") (pintype "input"))
      (node (ref "IC3") (pin "21") (pinfunction "RED_21") (pintype "output"))
      (node (ref "R74") (pin "2") (pinfunction "2_2") (pintype "passive"))
    )
    (net (code "135") (name "Net-(IC11-R2)") (class "Default")
      (node (ref "D26") (pin "A") (pinfunction "A_A") (pintype "passive"))
      (node (ref "IC11") (pin "12") (pinfunction "R2_12") (pintype "input"))
      (node (ref "R74") (pin "1") (pinfunction "1_1") (pintype "passive"))
    )
    (net (code "136") (name "Net-(IC11-Y)") (class "Default")
      (node (ref "IC11") (pin "6") (pinfunction "Y_6") (pintype "output"))
      (node (ref "R63") (pin "2") (pinfunction "2_2") (pintype "passive"))
    )
    (net (code "137") (name "Net-(IC12-CHB_O)") (class "Default")
      (node (ref "IC12") (pin "10") (pinfunction "CHB_O_10") (pintype "input"))
      (node (ref "R59") (pin "2") (pinfunction "2_2") (pintype "passive"))
    )
    (net (code "138") (name "Net-(IC12-CR_LAG)") (class "Default")
      (node (ref "C40") (pin "2") (pinfunction "2_2") (pintype "passive"))
      (node (ref "IC12") (pin "18") (pinfunction "CR_LAG_18") (pintype "output"))
      (node (ref "R56") (pin "2") (pinfunction "2_2") (pintype "passive"))
    )
    (net (code "139") (name "Net-(IC12-CR_LEAD)") (class "Default")
      (node (ref "C37") (pin "2") (pinfunction "2_2") (pintype "passive"))
      (node (ref "IC12") (pin "1") (pinfunction "CR_LEAD_1") (pintype "input"))
    )
    (net (code "140") (name "Net-(IC12-CR_OSC)") (class "Default")
      (node (ref "IC12") (pin "17") (pinfunction "CR_OSC_17") (pintype "input"))
      (node (ref "R72") (pin "1") (pinfunction "1_1") (pintype "passive"))
      (node (ref "R73_") (pin "1") (pinfunction "1_1") (pintype "passive"))
    )
    (net (code "141") (name "Net-(IC12-CR_SUBC)") (class "Default")
      (node (ref "IC12") (pin "13") (pinfunction "CR_SUBC_13") (pintype "input"))
      (node (ref "Q8") (pin "B") (pinfunction "B_B") (pintype "passive"))
      (node (ref "R63") (pin "1") (pinfunction "1_1") (pintype "passive"))
    )
    (net (code "142") (name "Net-(IC12-SNDTK)") (class "Default")
      (node (ref "D25_") (pin "K") (pinfunction "K_K") (pintype "bidirectional"))
      (node (ref "IC12") (pin "15") (pinfunction "SNDTK_15") (pintype "input"))
      (node (ref "L1") (pin "4") (pinfunction "E_4") (pintype "passive"))
    )
    (net (code "143") (name "Net-(IC12-TNKA1)") (class "Default")
      (node (ref "IC12") (pin "8") (pinfunction "TNKA1_8") (pintype "output"))
      (node (ref "IC12") (pin "9") (pinfunction "TNKA2_9") (pintype "input"))
    )
    (net (code "144") (name "Net-(IC12-TNKB1)") (class "Default")
      (node (ref "C41") (pin "2") (pinfunction "2_2") (pintype "passive"))
      (node (ref "IC12") (pin "6") (pinfunction "TNKB1_6") (pintype "output"))
      (node (ref "L3") (pin "1") (pinfunction "1_1") (pintype "passive"))
      (node (ref "R57") (pin "2") (pinfunction "2_2") (pintype "passive"))
    )
    (net (code "145") (name "Net-(IC12-TNKB2)") (class "Default")
      (node (ref "C41") (pin "1") (pinfunction "1_1") (pintype "passive"))
      (node (ref "IC12") (pin "7") (pinfunction "TNKB2_7") (pintype "input"))
      (node (ref "L3") (pin "2") (pinfunction "2_2") (pintype "passive"))
      (node (ref "R58") (pin "2") (pinfunction "2_2") (pintype "passive"))
    )
    (net (code "146") (name "Net-(IC25A-O)") (class "Default")
      (node (ref "IC25") (pin "12") (pinfunction "I0_12") (pintype "input"))
      (node (ref "IC25") (pin "3") (pinfunction "O_3") (pintype "output"))
    )
    (net (code "147") (name "Net-(IC25B-I1)") (class "Default")
      (node (ref "IC25") (pin "10") (pinfunction "I1_10") (pintype "input"))
      (node (ref "IC25") (pin "5") (pinfunction "I1_5") (pintype "input"))
      (node (ref "IC28") (pin "4") (pinfunction "O_4") (pintype "output"))
    )
    (net (code "148") (name "Net-(IC25C-I0)") (class "Default")
      (node (ref "IC25") (pin "9") (pinfunction "I0_9") (pintype "input"))
      (node (ref "IC28") (pin "2") (pinfunction "O_2") (pintype "output"))
    )
    (net (code "149") (name "Net-(IC25D-O)") (class "Default")
      (node (ref "IC25") (pin "11") (pinfunction "O_11") (pintype "output"))
      (node (ref "IC27") (pin "1") (pinfunction "I0_1") (pintype "input"))
    )
    (net (code "150") (name "Net-(IC26A-O)") (class "Default")
      (node (ref "IC26") (pin "3") (pinfunction "O_3") (pintype "output"))
      (node (ref "IC26") (pin "4") (pinfunction "I0_4") (pintype "input"))
    )
    (net (code "151") (name "Net-(IC26B-I1)") (class "Default")
      (node (ref "IC26") (pin "5") (pinfunction "I1_5") (pintype "input"))
      (node (ref "IC5") (pin "5") (pinfunction "Q_5") (pintype "output"))
    )
    (net (code "152") (name "Net-(IC26B-O)") (class "Default")
      (node (ref "IC26") (pin "6") (pinfunction "O_6") (pintype "output"))
      (node (ref "IC26") (pin "9") (pinfunction "I0_9") (pintype "input"))
    )
    (net (code "153") (name "Net-(IC26C-I1)") (class "Default")
      (node (ref "IC26") (pin "10") (pinfunction "I1_10") (pintype "input"))
      (node (ref "IC26") (pin "11") (pinfunction "O_11") (pintype "output"))
    )
    (net (code "154") (name "Net-(IC27A-I1)") (class "Default")
      (node (ref "C10") (pin "1") (pinfunction "1_1") (pintype "passive"))
      (node (ref "IC27") (pin "2") (pinfunction "I1_2") (pintype "input"))
      (node (ref "R28") (pin "2") (pinfunction "2_2") (pintype "passive"))
    )
    (net (code "155") (name "Net-(IC27C-I1)") (class "Default")
      (node (ref "C11") (pin "1") (pinfunction "1_1") (pintype "passive"))
      (node (ref "IC27") (pin "10") (pinfunction "I1_10") (pintype "input"))
      (node (ref "R45") (pin "2") (pinfunction "2_2") (pintype "passive"))
    )
    (net (code "156") (name "Net-(IC27C-O)") (class "Default")
      (node (ref "IC27") (pin "8") (pinfunction "O_8") (pintype "output"))
      (node (ref "IC28") (pin "3") (pinfunction "I_3") (pintype "input"))
    )
    (net (code "157") (name "Net-(IC28C-I)") (class "Default")
      (node (ref "IC28") (pin "5") (pinfunction "I_5") (pintype "input"))
      (node (ref "IC3") (pin "35") (pinfunction "GATE_35") (pintype "output"))
      (node (ref "IC4") (pin "11") (pinfunction "CLK_11") (pintype "input"))
    )
    (net (code "158") (name "Net-(IC28D-I)") (class "Default")
      (node (ref "C6") (pin "2") (pinfunction "2_2") (pintype "passive"))
      (node (ref "C7") (pin "2") (pinfunction "2_2") (pintype "passive"))
      (node (ref "IC28") (pin "9") (pinfunction "I_9") (pintype "input"))
      (node (ref "Q3") (pin "C") (pinfunction "C_C") (pintype "passive"))
      (node (ref "R43") (pin "1") (pinfunction "1_1") (pintype "passive"))
      (node (ref "R44") (pin "1") (pinfunction "1_1") (pintype "passive"))
    )
    (net (code "159") (name "Net-(IC28D-O)") (class "Default")
      (node (ref "IC28") (pin "11") (pinfunction "I_11") (pintype "input"))
      (node (ref "IC28") (pin "8") (pinfunction "O_8") (pintype "output"))
      (node (ref "JP") (pin "3") (pinfunction "3_3") (pintype "passive"))
    )
    (net (code "160") (name "Net-(IC28E-O)") (class "Default")
      (node (ref "IC28") (pin "10") (pinfunction "O_10") (pintype "output"))
      (node (ref "IC3") (pin "11") (pinfunction "CLK_11") (pintype "input"))
      (node (ref "JP") (pin "1") (pinfunction "1_1") (pintype "passive"))
      (node (ref "JP") (pin "2") (pinfunction "2_2") (pintype "passive"))
      (node (ref "TP2") (pin "1") (pinfunction "TP_1") (pintype "input"))
    )
    (net (code "161") (name "Net-(J4-Pad2)") (class "Default")
      (node (ref "J4") (pin "2") (pinfunction "2_2") (pintype "passive"))
      (node (ref "MIC") (pin "TIP") (pinfunction "TIP_TIP") (pintype "passive"))
    )
    (net (code "162") (name "Net-(MIC-PadNC)") (class "Default")
      (node (ref "MIC") (pin "NC") (pinfunction "NC_NC") (pintype "passive"))
      (node (ref "R46") (pin "1") (pinfunction "1_1") (pintype "passive"))
      (node (ref "R69") (pin "2") (pinfunction "2_2") (pintype "passive"))
    )
    (net (code "163") (name "Net-(PE-M)") (class "Default")
      (node (ref "D6") (pin "A") (pinfunction "A_A") (pintype "bidirectional"))
      (node (ref "KB2") (pin "5") (pinfunction "5_5") (pintype "passive"))
      (node (ref "P") (pin "5") (pinfunction "M_5") (pintype "passive"))
      (node (ref "P") (pin "8") (pinfunction "M_8") (pintype "passive"))
      (node (ref "P") (pin "9") (pinfunction "M_9") (pintype "passive"))
    )
    (net (code "164") (name "Net-(PG-M)") (class "Default")
      (node (ref "D5") (pin "A") (pinfunction "A_A") (pintype "bidirectional"))
      (node (ref "KB2") (pin "8") (pinfunction "8_8") (pintype "passive"))
      (node (ref "P") (pin "7") (pinfunction "M_7") (pintype "passive"))
    )
    (net (code "165") (name "Net-(Q2-B)") (class "Default")
      (node (ref "C9") (pin "1") (pinfunction "1_1") (pintype "passive"))
      (node (ref "Q2") (pin "2") (pinfunction "B_2") (pintype "passive"))
      (node (ref "R49") (pin "1") (pinfunction "1_1") (pintype "passive"))
      (node (ref "R50") (pin "2") (pinfunction "2_2") (pintype "passive"))
    )
    (net (code "166") (name "Net-(Q3-PadE)") (class "Default")
      (node (ref "Q3") (pin "E") (pinfunction "E_E") (pintype "passive"))
      (node (ref "R47") (pin "2") (pinfunction "2_2") (pintype "passive"))
    )
    (net (code "167") (name "Net-(Q4-B)") (class "Default")
      (node (ref "C47") (pin "2") (pinfunction "2_2") (pintype "passive"))
      (node (ref "Q4") (pin "2") (pinfunction "B_2") (pintype "passive"))
      (node (ref "R64") (pin "1") (pinfunction "1_1") (pintype "passive"))
      (node (ref "R65") (pin "1") (pinfunction "1_1") (pintype "passive"))
    )
    (net (code "168") (name "Net-(Q4-C)") (class "Default")
      (node (ref "Q4") (pin "3") (pinfunction "C_3") (pintype "passive"))
      (node (ref "Q5") (pin "B") (pinfunction "B_B") (pintype "passive"))
      (node (ref "Q6") (pin "B") (pinfunction "B_B") (pintype "passive"))
      (node (ref "R66") (pin "2") (pinfunction "2_2") (pintype "passive"))
    )
    (net (code "169") (name "Net-(U$1Y-EDGE)") (class "Default")
      (node (ref "C55") (pin "2") (pinfunction "2_2") (pintype "passive"))
      (node (ref "U$1") (pin "4B") (pinfunction "EDGE_4B") (pintype "bidirectional"))
    )
    (net (code "170") (name "Net-(X1-1)") (class "Default")
      (node (ref "C58") (pin "-") (pinfunction "-_-") (pintype "passive"))
      (node (ref "X1") (pin "PIN") (pinfunction "1_PIN") (pintype "passive"))
    )
    (net (code "171") (name "V+") (class "Default")
      (node (ref "7805") (pin "IN") (pinfunction "IN_IN") (pintype "input"))
      (node (ref "C2") (pin "+") (pinfunction "+_+") (pintype "passive"))
      (node (ref "C3") (pin "2") (pinfunction "2_2") (pintype "passive"))
      (node (ref "D22") (pin "A") (pinfunction "A_A") (pintype "bidirectional"))
      (node (ref "JP2") (pin "3") (pinfunction "3_3") (pintype "passive"))
      (node (ref "Q5") (pin "C") (pinfunction "C_C") (pintype "passive"))
      (node (ref "R66") (pin "1") (pinfunction "1_1") (pintype "passive"))
      (node (ref "U$1") (pin "4A") (pinfunction "EDGE_4A") (pintype "bidirectional"))
      (node (ref "X2") (pin "TIP") (pinfunction "TIP_TIP") (pintype "passive"))
    )
    (net (code "172") (name "VDD") (class "Default")
      (node (ref "C23") (pin "1") (pinfunction "1_1") (pintype "passive"))
      (node (ref "C25") (pin "1") (pinfunction "1_1") (pintype "passive"))
      (node (ref "C28") (pin "1") (pinfunction "1_1") (pintype "passive"))
      (node (ref "C30") (pin "1") (pinfunction "1_1") (pintype "passive"))
      (node (ref "IC13") (pin "8") (pinfunction "VDD_8") (pintype "power_in"))
      (node (ref "IC14") (pin "8") (pinfunction "VDD_8") (pintype "power_in"))
      (node (ref "IC15") (pin "8") (pinfunction "VDD_8") (pintype "power_in"))
      (node (ref "IC16") (pin "8") (pinfunction "VDD_8") (pintype "power_in"))
      (node (ref "IC17") (pin "8") (pinfunction "VDD_8") (pintype "power_in"))
      (node (ref "IC18") (pin "8") (pinfunction "VDD_8") (pintype "power_in"))
      (node (ref "IC19") (pin "8") (pinfunction "VDD_8") (pintype "power_in"))
      (node (ref "IC20") (pin "8") (pinfunction "VDD_8") (pintype "power_in"))
      (node (ref "JP2") (pin "2") (pinfunction "2_2") (pintype "passive"))
    )
    (net (code "173") (name "unconnected-(IC3-~{50}{slash}60HZ-Pad1)") (class "Default")
      (node (ref "IC3") (pin "1") (pinfunction "~{50}/60HZ_1") (pintype "input"))
    )
    (net (code "174") (name "unconnected-(IC4A-CLK-Pad3)") (class "Default")
      (node (ref "IC4") (pin "3") (pinfunction "CLK_3") (pintype "input"))
    )
    (net (code "175") (name "unconnected-(IC4A-CLR-Pad1)") (class "Default")
      (node (ref "IC4") (pin "1") (pinfunction "CLR_1") (pintype "input"))
    )
    (net (code "176") (name "unconnected-(IC4A-D-Pad2)") (class "Default")
      (node (ref "IC4") (pin "2") (pinfunction "D_2") (pintype "input"))
    )
    (net (code "177") (name "unconnected-(IC4A-PRE-Pad4)") (class "Default")
      (node (ref "IC4") (pin "4") (pinfunction "PRE_4") (pintype "input"))
    )
    (net (code "178") (name "unconnected-(IC4A-Q-Pad5)") (class "Default")
      (node (ref "IC4") (pin "5") (pinfunction "Q_5") (pintype "output"))
    )
    (net (code "179") (name "unconnected-(IC4A-~{Q}-Pad6)") (class "Default")
      (node (ref "IC4") (pin "6") (pinfunction "~{Q}_6") (pintype "output"))
    )
    (net (code "180") (name "unconnected-(IC5B-~{Q}-Pad8)") (class "Default")
      (node (ref "IC5") (pin "8") (pinfunction "~{Q}_8") (pintype "output"))
    )
    (net (code "181") (name "unconnected-(IC6A-1A-Pad2)") (class "Default")
      (node (ref "IC6") (pin "2") (pinfunction "1A_2") (pintype "input"))
    )
    (net (code "182") (name "unconnected-(IC6A-1B-Pad3)") (class "Default")
      (node (ref "IC6") (pin "3") (pinfunction "1B_3") (pintype "input"))
    )
    (net (code "183") (name "unconnected-(IC6A-1Y-Pad4)") (class "Default")
      (node (ref "IC6") (pin "4") (pinfunction "1Y_4") (pintype "output"))
    )
    (net (code "184") (name "unconnected-(IC6A-3A-Pad11)") (class "Default")
      (node (ref "IC6") (pin "11") (pinfunction "3A_11") (pintype "input"))
    )
    (net (code "185") (name "unconnected-(IC6A-3B-Pad10)") (class "Default")
      (node (ref "IC6") (pin "10") (pinfunction "3B_10") (pintype "input"))
    )
    (net (code "186") (name "unconnected-(IC6A-3Y-Pad9)") (class "Default")
      (node (ref "IC6") (pin "9") (pinfunction "3Y_9") (pintype "output"))
    )
    (net (code "187") (name "unconnected-(IC9A-1A-Pad2)") (class "Default")
      (node (ref "IC9") (pin "2") (pinfunction "1A_2") (pintype "input"))
    )
    (net (code "188") (name "unconnected-(IC9A-1B-Pad3)") (class "Default")
      (node (ref "IC9") (pin "3") (pinfunction "1B_3") (pintype "input"))
    )
    (net (code "189") (name "unconnected-(IC9A-1Y-Pad4)") (class "Default")
      (node (ref "IC9") (pin "4") (pinfunction "1Y_4") (pintype "output"))
    )
    (net (code "190") (name "unconnected-(IC12-CHA_O-Pad11)") (class "Default")
      (node (ref "IC12") (pin "11") (pinfunction "CHA_O_11") (pintype "input"))
    )
    (net (code "191") (name "unconnected-(L1B-S1-PadS2)") (class "Default")
      (node (ref "L1") (pin "S2") (pinfunction "S1_S2") (pintype "passive"))
    )
    (net (code "192") (name "unconnected-(L1B-S2-PadS1)") (class "Default")
      (node (ref "L1") (pin "S1") (pinfunction "S2_S1") (pintype "passive"))
    )
    (net (code "193") (name "unconnected-(U$1AX-EDGE-Pad28B)") (class "Default")
      (node (ref "U$1") (pin "28B") (pinfunction "EDGE_28B") (pintype "bidirectional"))
    )
    (net (code "194") (name "unconnected-(U$1F-EDGE-Pad15A)") (class "Default")
      (node (ref "U$1") (pin "15A") (pinfunction "EDGE_15A") (pintype "bidirectional"))
    )
    (net (code "195") (name "unconnected-(U$1G-EDGE-Pad16A)") (class "Default")
      (node (ref "U$1") (pin "16A") (pinfunction "EDGE_16A") (pintype "bidirectional"))
    )
    (net (code "196") (name "unconnected-(U$1H-EDGE-Pad17A)") (class "Default")
      (node (ref "U$1") (pin "17A") (pinfunction "EDGE_17A") (pintype "bidirectional"))
    )
    (net (code "197") (name "unconnected-(U$1I-EDGE-Pad18A)") (class "Default")
      (node (ref "U$1") (pin "18A") (pinfunction "EDGE_18A") (pintype "bidirectional"))
    )
    (net (code "198") (name "unconnected-(X2-PadNC)") (class "Default")
      (node (ref "X2") (pin "NC") (pinfunction "NC_NC") (pintype "passive"))
    )
  )
)
